# EEZ_DIB_AFE1_r1B3.net
KiCad netlist of a schematic drawn in EAGLE
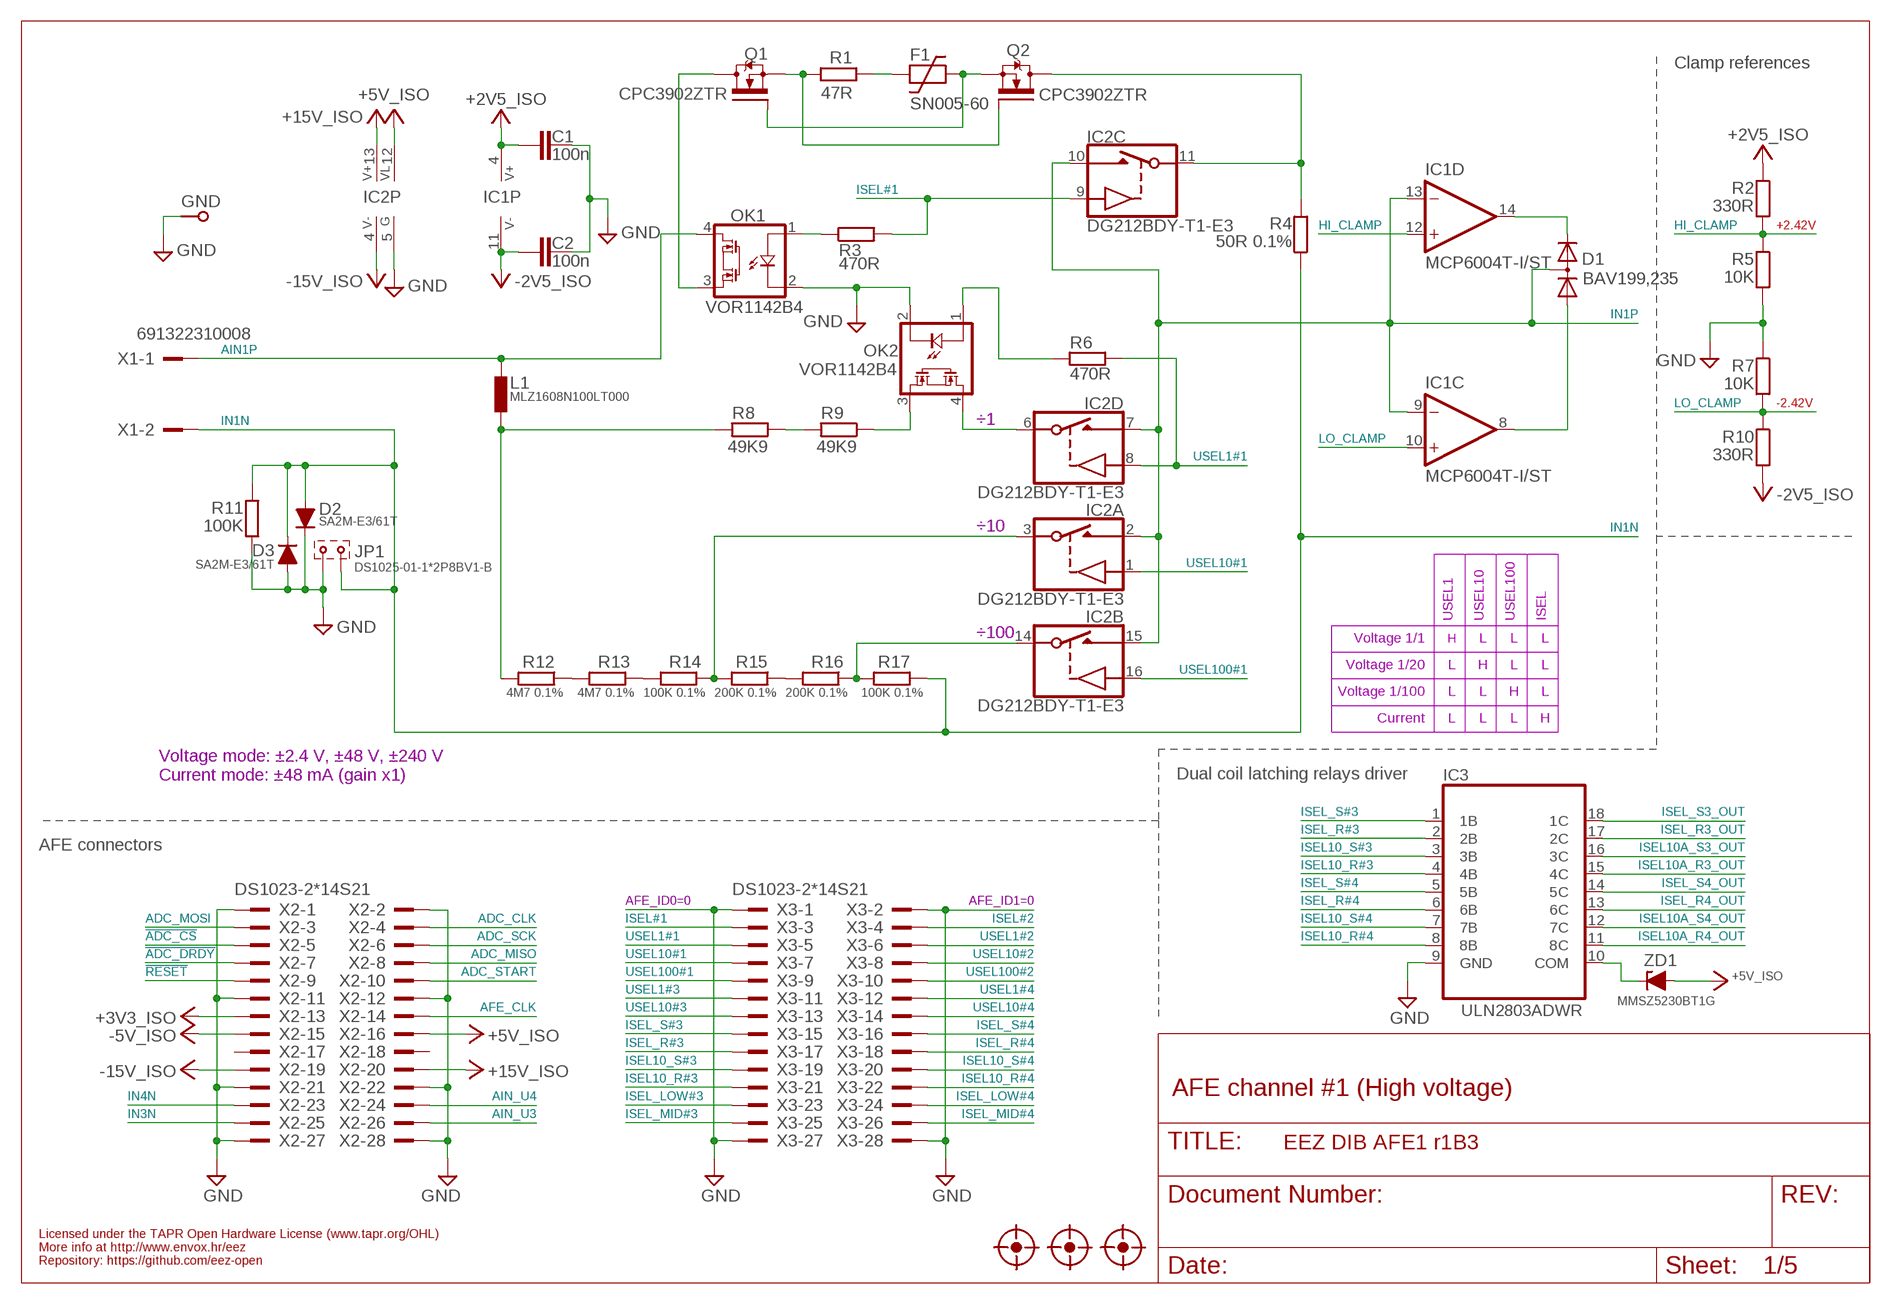
[diagram p0: schematic, sheet 1]
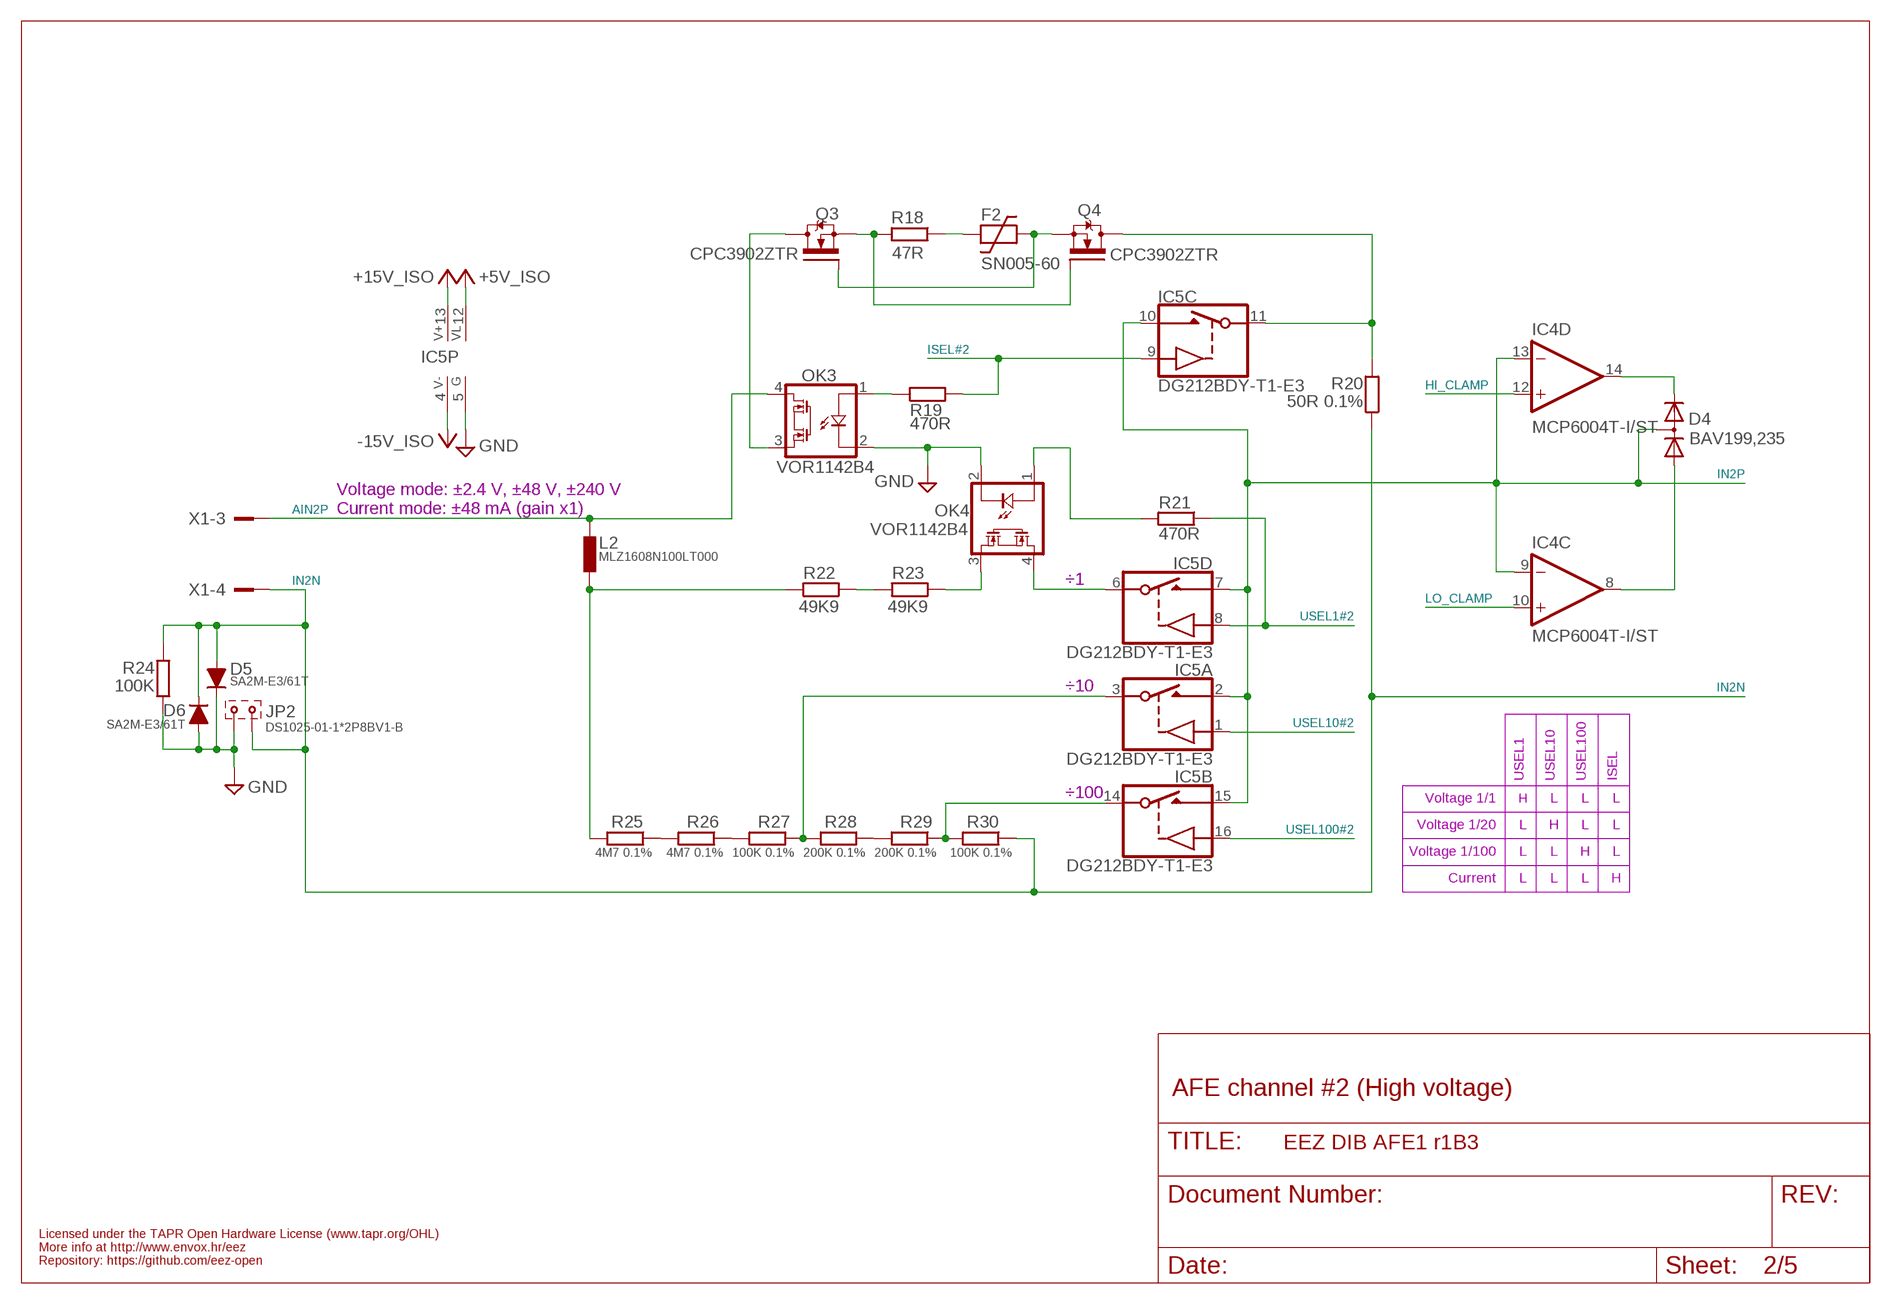
[diagram p1: schematic, sheet 2]
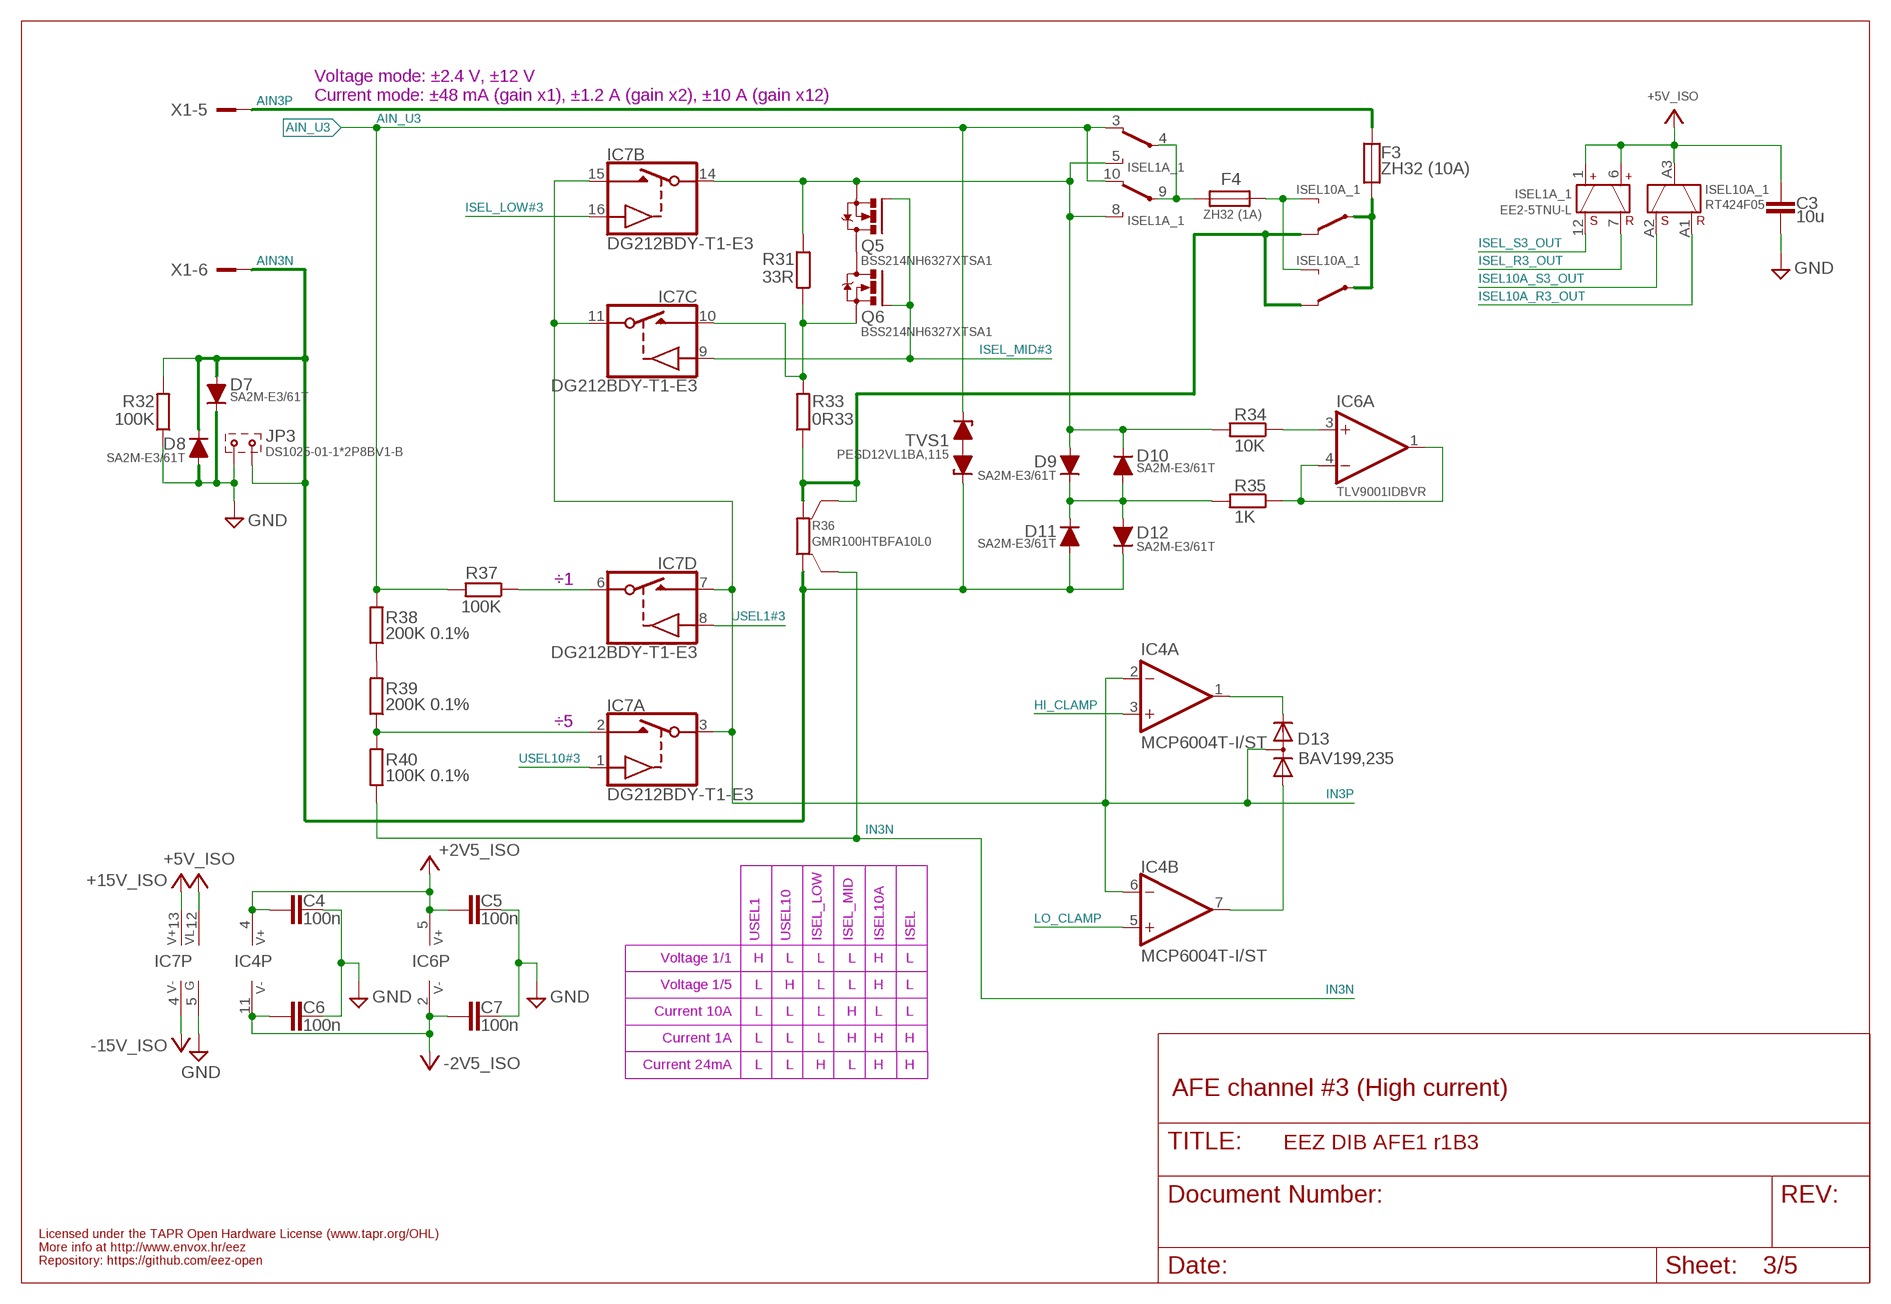
[diagram p2: schematic, sheet 3]
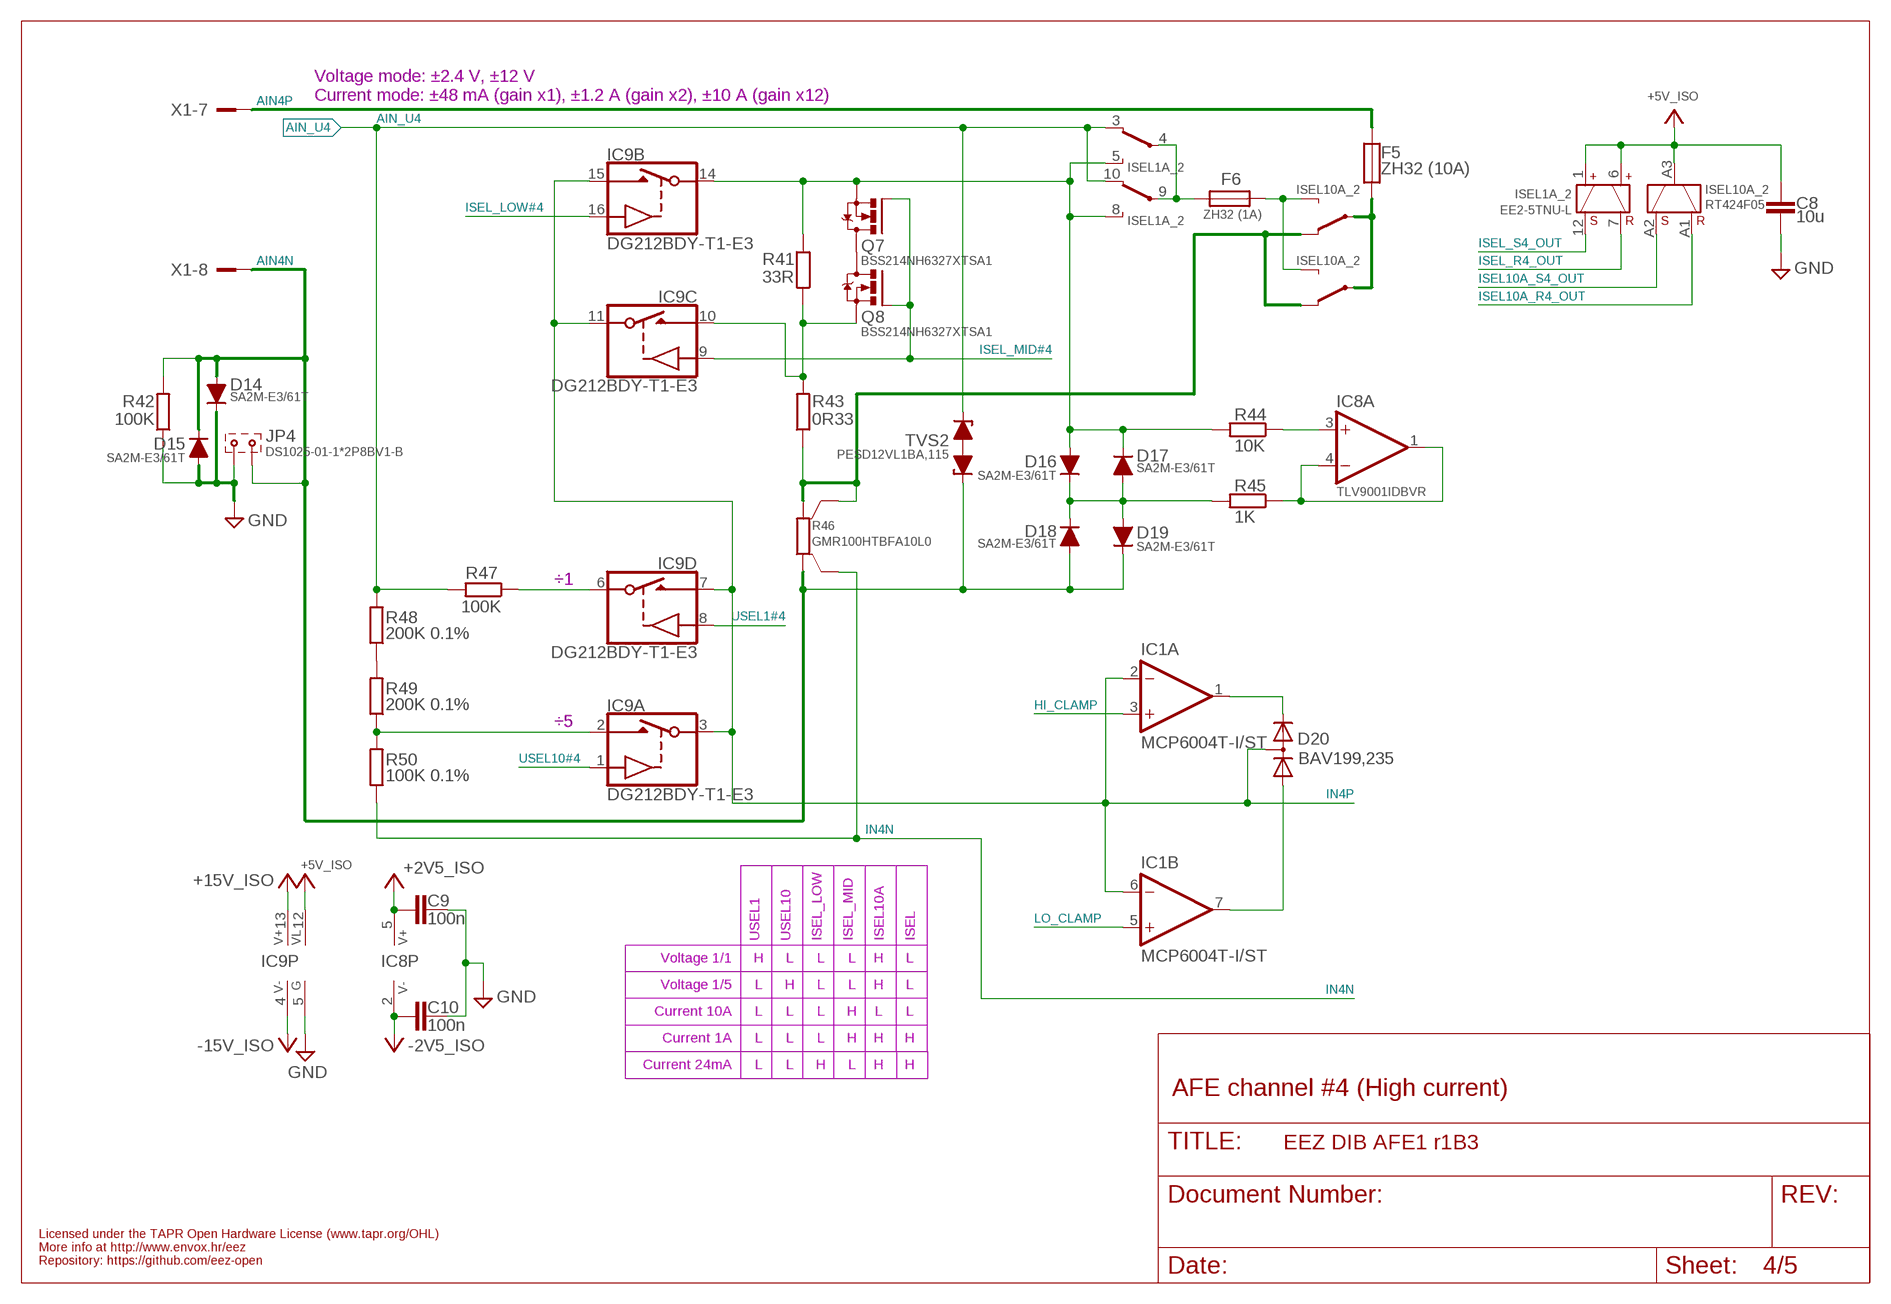
[diagram p3: schematic, sheet 4]
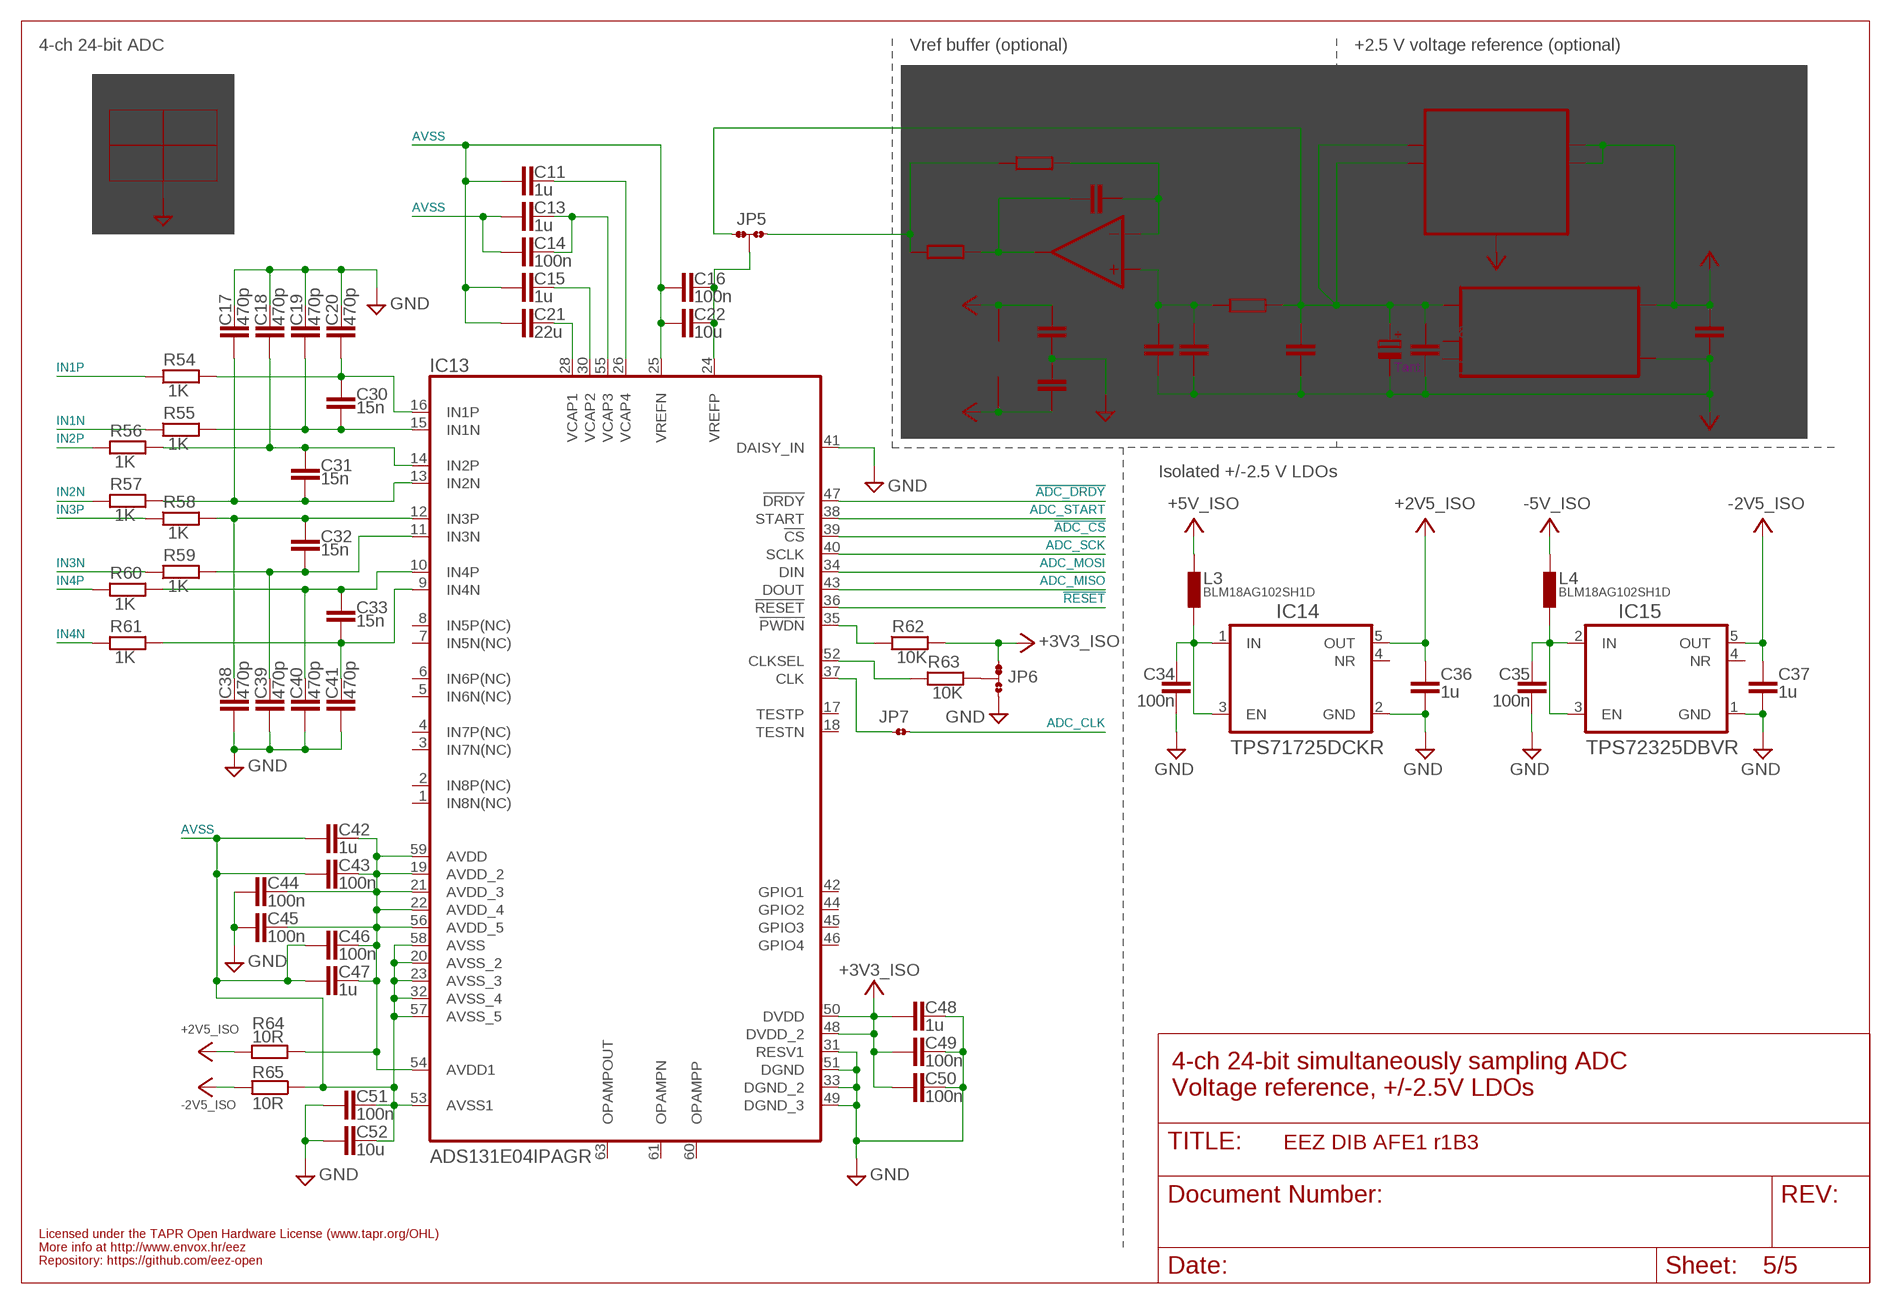
[diagram p4: schematic, sheet 5]

(export (version "E")
  (design (tool "Eeschema 10.0.6"))
  (components
    (comp (ref "C3")
      (value "10u")
      (footprint "eagle-import:C1206")
      (libsource (lib "eagle-import") (part "C-EUC1206"))
    )
    (comp (ref "C4")
      (value "100n")
      (footprint "eagle-import:C0603")
      (libsource (lib "eagle-import") (part "C-EUC0603"))
    )
    (comp (ref "C5")
      (value "100n")
      (footprint "eagle-import:C0603")
      (libsource (lib "eagle-import") (part "C-EUC0603"))
    )
    (comp (ref "C6")
      (value "100n")
      (footprint "eagle-import:C0603")
      (libsource (lib "eagle-import") (part "C-EUC0603"))
    )
    (comp (ref "C7")
      (value "100n")
      (footprint "eagle-import:C0603")
      (libsource (lib "eagle-import") (part "C-EUC0603"))
    )
    (comp (ref "D7")
      (value "SA2M-E3/61T")
      (footprint "eagle-import:SMA_NARROW")
      (libsource (lib "eagle-import") (part "DIODE_SMA-NARROW"))
    )
    (comp (ref "D8")
      (value "SA2M-E3/61T")
      (footprint "eagle-import:SMA_NARROW")
      (libsource (lib "eagle-import") (part "DIODE_SMA-NARROW"))
    )
    (comp (ref "D9")
      (value "SA2M-E3/61T")
      (footprint "eagle-import:SMA_NARROW")
      (libsource (lib "eagle-import") (part "DIODE_SMA-NARROW"))
    )
    (comp (ref "D10")
      (value "SA2M-E3/61T")
      (footprint "eagle-import:SMA_NARROW")
      (libsource (lib "eagle-import") (part "DIODE_SMA-NARROW"))
    )
    (comp (ref "D11")
      (value "SA2M-E3/61T")
      (footprint "eagle-import:SMA_NARROW")
      (libsource (lib "eagle-import") (part "DIODE_SMA-NARROW"))
    )
    (comp (ref "D12")
      (value "SA2M-E3/61T")
      (footprint "eagle-import:SMA_NARROW")
      (libsource (lib "eagle-import") (part "DIODE_SMA-NARROW"))
    )
    (comp (ref "D13")
      (value "BAV199,235")
      (footprint "eagle-import:SOT23")
      (libsource (lib "eagle-import") (part "BAV199"))
    )
    (comp (ref "F3")
      (value "ZH32 (10A)")
      (footprint "eagle-import:ZH32")
      (libsource (lib "eagle-import") (part "ZH32"))
    )
    (comp (ref "F4")
      (value "ZH32 (1A)")
      (footprint "eagle-import:ZH32")
      (libsource (lib "eagle-import") (part "ZH32"))
    )
    (comp (ref "IC4")
      (value "MCP6004T-I/ST")
      (footprint "eagle-import:PW(R-PDSO-G14)")
      (libsource (lib "eagle-import") (part "OPA4197PW"))
    )
    (comp (ref "IC6")
      (value "TLV9001IDBVR")
      (footprint "eagle-import:DBV5")
      (libsource (lib "eagle-import") (part "OPA376AIDBVR"))
    )
    (comp (ref "IC7")
      (value "DG212BDY-T1-E3")
      (footprint "eagle-import:SO16")
      (libsource (lib "eagle-import") (part "DG212BDY-T1-E3"))
    )
    (comp (ref "ISEL1A_1")
      (value "EE2-5TNU-L")
      (footprint "eagle-import:G6SK-2F")
      (libsource (lib "eagle-import") (part "G6SK-2F"))
    )
    (comp (ref "ISEL10A_1")
      (value "RT424F05")
      (footprint "eagle-import:RT424FXX")
      (libsource (lib "eagle-import") (part "RT424FXX"))
    )
    (comp (ref "JP3")
      (value "DS1025-01-1*2P8BV1-B")
      (footprint "eagle-import:2MM-2")
      (libsource (lib "eagle-import") (part "JUMPER-2PIN-2MM"))
    )
    (comp (ref "Q5")
      (value "BSS214NH6327XTSA1")
      (footprint "eagle-import:SOT103P240X110-3N")
      (fields
        (field (name "MPN") "2N7002-7-F")
        (field (name "MPN_1") "2N7002-7-F")
        (field (name "OC_FARNELL") "1713823")
        (field (name "OC_NEWARK") "25R5679")
        (field (name "PACKAGE") "SOT-23-3")
        (field (name "SUPPLIER") "DIODES INC.")
      )
      (libsource (lib "eagle-import") (part "2N7002"))
    )
    (comp (ref "Q6")
      (value "BSS214NH6327XTSA1")
      (footprint "eagle-import:SOT103P240X110-3N")
      (fields (field (name "MPN") "2N7002-7-F"))
      (libsource (lib "eagle-import") (part "2N7002"))
    )
    (comp (ref "R31")
      (value "33R")
      (footprint "eagle-import:R1206")
      (libsource (lib "eagle-import") (part "R-EU_R1206"))
    )
    (comp (ref "R32")
      (value "100K")
      (footprint "eagle-import:R1206")
      (libsource (lib "eagle-import") (part "R-EU_R1206"))
    )
    (comp (ref "R33")
      (value "0R33")
      (footprint "eagle-import:R1210")
      (libsource (lib "eagle-import") (part "R-EU_R1210"))
    )
    (comp (ref "R34")
      (value "10K")
      (footprint "eagle-import:R0805")
      (libsource (lib "eagle-import") (part "R-EU_R0805"))
    )
    (comp (ref "R35")
      (value "1K")
      (footprint "eagle-import:R0805")
      (libsource (lib "eagle-import") (part "R-EU_R0805"))
    )
    (comp (ref "R36")
      (value "GMR100HTBFA10L0")
      (footprint "eagle-import:R_2512-4WIRE")
      (libsource (lib "eagle-import") (part "R-EU_4WIRE2512"))
    )
    (comp (ref "R37")
      (value "100K")
      (footprint "eagle-import:R1206")
      (libsource (lib "eagle-import") (part "R-EU_R1206"))
    )
    (comp (ref "R38")
      (value "200K 0.1%")
      (footprint "eagle-import:R1206")
      (libsource (lib "eagle-import") (part "R-EU_R1206"))
    )
    (comp (ref "R39")
      (value "200K 0.1%")
      (footprint "eagle-import:R1206")
      (libsource (lib "eagle-import") (part "R-EU_R1206"))
    )
    (comp (ref "R40")
      (value "100K 0.1%")
      (footprint "eagle-import:R1206")
      (libsource (lib "eagle-import") (part "R-EU_R1206"))
    )
    (comp (ref "TVS1")
      (value "PESD12VL1BA,115")
      (footprint "eagle-import:SOD323-BIDIR")
      (libsource (lib "eagle-import") (part "PESDXL1BA"))
    )
    (comp (ref "X1")
      (value "691322310008")
      (footprint "eagle-import:691322310008")
      (libsource (lib "eagle-import") (part "691322310008"))
    )
    (comp (ref "D4")
      (value "BAV199,235")
      (footprint "eagle-import:SOT23")
      (libsource (lib "eagle-import") (part "BAV199"))
    )
    (comp (ref "D5")
      (value "SA2M-E3/61T")
      (footprint "eagle-import:SMA_NARROW")
      (libsource (lib "eagle-import") (part "DIODE_SMA-NARROW"))
    )
    (comp (ref "D6")
      (value "SA2M-E3/61T")
      (footprint "eagle-import:SMA_NARROW")
      (libsource (lib "eagle-import") (part "DIODE_SMA-NARROW"))
    )
    (comp (ref "F2")
      (value "SN005-60")
      (footprint "eagle-import:C1206-HV")
      (libsource (lib "eagle-import") (part "FUSE_RESETTABLE2"))
    )
    (comp (ref "IC5")
      (value "DG212BDY-T1-E3")
      (footprint "eagle-import:SO16")
      (libsource (lib "eagle-import") (part "DG212BDY-T1-E3"))
    )
    (comp (ref "JP2")
      (value "DS1025-01-1*2P8BV1-B")
      (footprint "eagle-import:2MM-2")
      (libsource (lib "eagle-import") (part "JUMPER-2PIN-2MM"))
    )
    (comp (ref "L2")
      (value "MLZ1608N100LT000")
      (footprint "eagle-import:BEAD0603")
      (libsource (lib "eagle-import") (part "FERRITE_BEAD0603"))
    )
    (comp (ref "OK3")
      (value "VOR1142B4")
      (footprint "eagle-import:DIL4-SMD")
      (libsource (lib "eagle-import") (part "VOR1142B4"))
    )
    (comp (ref "OK4")
      (value "VOR1142B4")
      (footprint "eagle-import:DIL4-SMD")
      (libsource (lib "eagle-import") (part "VOR1142B4"))
    )
    (comp (ref "Q3")
      (value "CPC3902ZTR")
      (footprint "eagle-import:SOT230P700X180-4N")
      (libsource (lib "eagle-import") (part "BSP129SOT-223"))
    )
    (comp (ref "Q4")
      (value "CPC3902ZTR")
      (footprint "eagle-import:SOT230P700X180-4N")
      (libsource (lib "eagle-import") (part "BSP129SOT-223"))
    )
    (comp (ref "R18")
      (value "47R")
      (footprint "eagle-import:R0805")
      (libsource (lib "eagle-import") (part "R-EU_R0805"))
    )
    (comp (ref "R19")
      (value "470R")
      (footprint "eagle-import:R0805")
      (libsource (lib "eagle-import") (part "R-EU_R0805"))
    )
    (comp (ref "R20")
      (value "50R 0.1%")
      (footprint "eagle-import:R1206")
      (libsource (lib "eagle-import") (part "R-EU_R1206"))
    )
    (comp (ref "R21")
      (value "470R")
      (footprint "eagle-import:R0805")
      (libsource (lib "eagle-import") (part "R-EU_R0805"))
    )
    (comp (ref "R22")
      (value "49K9")
      (footprint "eagle-import:R1206")
      (libsource (lib "eagle-import") (part "R-EU_R1206"))
    )
    (comp (ref "R23")
      (value "49K9")
      (footprint "eagle-import:R1206")
      (libsource (lib "eagle-import") (part "R-EU_R1206"))
    )
    (comp (ref "R24")
      (value "100K")
      (footprint "eagle-import:R1206")
      (libsource (lib "eagle-import") (part "R-EU_R1206"))
    )
    (comp (ref "R25")
      (value "4M7 0.1%")
      (footprint "eagle-import:R1206")
      (libsource (lib "eagle-import") (part "R-EU_R1206"))
    )
    (comp (ref "R26")
      (value "4M7 0.1%")
      (footprint "eagle-import:R1206")
      (libsource (lib "eagle-import") (part "R-EU_R1206"))
    )
    (comp (ref "R27")
      (value "100K 0.1%")
      (footprint "eagle-import:R1206")
      (libsource (lib "eagle-import") (part "R-EU_R1206"))
    )
    (comp (ref "R28")
      (value "200K 0.1%")
      (footprint "eagle-import:R1206")
      (libsource (lib "eagle-import") (part "R-EU_R1206"))
    )
    (comp (ref "R29")
      (value "200K 0.1%")
      (footprint "eagle-import:R1206")
      (libsource (lib "eagle-import") (part "R-EU_R1206"))
    )
    (comp (ref "R30")
      (value "100K 0.1%")
      (footprint "eagle-import:R1206")
      (libsource (lib "eagle-import") (part "R-EU_R1206"))
    )
    (comp (ref "C11")
      (value "1u")
      (footprint "eagle-import:C0805")
      (libsource (lib "eagle-import") (part "C-EUC0805"))
    )
    (comp (ref "C12")
      (value "N.C.")
      (footprint "eagle-import:C0805")
      (libsource (lib "eagle-import") (part "C-EUC0805"))
    )
    (comp (ref "C13")
      (value "1u")
      (footprint "eagle-import:C0805")
      (libsource (lib "eagle-import") (part "C-EUC0805"))
    )
    (comp (ref "C14")
      (value "100n")
      (footprint "eagle-import:C0603")
      (libsource (lib "eagle-import") (part "C-EUC0603"))
    )
    (comp (ref "C15")
      (value "1u")
      (footprint "eagle-import:C0805")
      (libsource (lib "eagle-import") (part "C-EUC0805"))
    )
    (comp (ref "C16")
      (value "100n")
      (footprint "eagle-import:C0603")
      (libsource (lib "eagle-import") (part "C-EUC0603"))
    )
    (comp (ref "C17")
      (value "470p")
      (footprint "eagle-import:C0603")
      (libsource (lib "eagle-import") (part "C-EUC0603"))
    )
    (comp (ref "C18")
      (value "470p")
      (footprint "eagle-import:C0603")
      (libsource (lib "eagle-import") (part "C-EUC0603"))
    )
    (comp (ref "C19")
      (value "470p")
      (footprint "eagle-import:C0603")
      (libsource (lib "eagle-import") (part "C-EUC0603"))
    )
    (comp (ref "C20")
      (value "470p")
      (footprint "eagle-import:C0603")
      (libsource (lib "eagle-import") (part "C-EUC0603"))
    )
    (comp (ref "C21")
      (value "22u")
      (footprint "eagle-import:C1206")
      (libsource (lib "eagle-import") (part "C-EUC1206"))
    )
    (comp (ref "C22")
      (value "10u")
      (footprint "eagle-import:C1206")
      (libsource (lib "eagle-import") (part "C-EUC1206"))
    )
    (comp (ref "C23")
      (value "N.C.")
      (footprint "eagle-import:C0603")
      (libsource (lib "eagle-import") (part "C-EUC0603"))
    )
    (comp (ref "C24")
      (value "N.C.")
      (footprint "eagle-import:C1206")
      (libsource (lib "eagle-import") (part "C-EUC1206"))
    )
    (comp (ref "C25")
      (value "N.C.")
      (footprint "eagle-import:C1206")
      (libsource (lib "eagle-import") (part "C-EUC1206"))
    )
    (comp (ref "C26")
      (value "N.C.")
      (footprint "eagle-import:C1206")
      (libsource (lib "eagle-import") (part "C-EUC1206"))
    )
    (comp (ref "C27")
      (value "N.C.")
      (footprint "eagle-import:C1206")
      (libsource (lib "eagle-import") (part "C-EUC1206"))
    )
    (comp (ref "C28")
      (value "N.C.")
      (footprint "eagle-import:EC1206")
      (libsource (lib "eagle-import") (part "ECAP1206"))
    )
    (comp (ref "C28A")
      (value "N.C.")
      (footprint "eagle-import:C050-075X110")
      (libsource (lib "eagle-import") (part "C-EU7.5X11"))
    )
    (comp (ref "C29")
      (value "N.C.")
      (footprint "eagle-import:C0603")
      (libsource (lib "eagle-import") (part "C-EUC0603"))
    )
    (comp (ref "C30")
      (value "15n")
      (footprint "eagle-import:C0603")
      (libsource (lib "eagle-import") (part "C-EUC0603"))
    )
    (comp (ref "C31")
      (value "15n")
      (footprint "eagle-import:C0603")
      (libsource (lib "eagle-import") (part "C-EUC0603"))
    )
    (comp (ref "C32")
      (value "15n")
      (footprint "eagle-import:C0603")
      (libsource (lib "eagle-import") (part "C-EUC0603"))
    )
    (comp (ref "C33")
      (value "15n")
      (footprint "eagle-import:C0603")
      (libsource (lib "eagle-import") (part "C-EUC0603"))
    )
    (comp (ref "C34")
      (value "100n")
      (footprint "eagle-import:C0603")
      (libsource (lib "eagle-import") (part "C-EUC0603"))
    )
    (comp (ref "C35")
      (value "100n")
      (footprint "eagle-import:C0603")
      (libsource (lib "eagle-import") (part "C-EUC0603"))
    )
    (comp (ref "C36")
      (value "1u")
      (footprint "eagle-import:C0805")
      (libsource (lib "eagle-import") (part "C-EUC0805"))
    )
    (comp (ref "C37")
      (value "1u")
      (footprint "eagle-import:C0805")
      (libsource (lib "eagle-import") (part "C-EUC0805"))
    )
    (comp (ref "C38")
      (value "470p")
      (footprint "eagle-import:C0603")
      (libsource (lib "eagle-import") (part "C-EUC0603"))
    )
    (comp (ref "C39")
      (value "470p")
      (footprint "eagle-import:C0603")
      (libsource (lib "eagle-import") (part "C-EUC0603"))
    )
    (comp (ref "C40")
      (value "470p")
      (footprint "eagle-import:C0603")
      (libsource (lib "eagle-import") (part "C-EUC0603"))
    )
    (comp (ref "C41")
      (value "470p")
      (footprint "eagle-import:C0603")
      (libsource (lib "eagle-import") (part "C-EUC0603"))
    )
    (comp (ref "C42")
      (value "1u")
      (footprint "eagle-import:C0805")
      (libsource (lib "eagle-import") (part "C-EUC0805"))
    )
    (comp (ref "C43")
      (value "100n")
      (footprint "eagle-import:C0603")
      (libsource (lib "eagle-import") (part "C-EUC0603"))
    )
    (comp (ref "C44")
      (value "100n")
      (footprint "eagle-import:C0603")
      (libsource (lib "eagle-import") (part "C-EUC0603"))
    )
    (comp (ref "C45")
      (value "100n")
      (footprint "eagle-import:C0603")
      (libsource (lib "eagle-import") (part "C-EUC0603"))
    )
    (comp (ref "C46")
      (value "100n")
      (footprint "eagle-import:C0603")
      (libsource (lib "eagle-import") (part "C-EUC0603"))
    )
    (comp (ref "C47")
      (value "1u")
      (footprint "eagle-import:C0805")
      (libsource (lib "eagle-import") (part "C-EUC0805"))
    )
    (comp (ref "C48")
      (value "1u")
      (footprint "eagle-import:C0805")
      (libsource (lib "eagle-import") (part "C-EUC0805"))
    )
    (comp (ref "C49")
      (value "100n")
      (footprint "eagle-import:C0603")
      (libsource (lib "eagle-import") (part "C-EUC0603"))
    )
    (comp (ref "C50")
      (value "100n")
      (footprint "eagle-import:C0603")
      (libsource (lib "eagle-import") (part "C-EUC0603"))
    )
    (comp (ref "C51")
      (value "100n")
      (footprint "eagle-import:C0603")
      (libsource (lib "eagle-import") (part "C-EUC0603"))
    )
    (comp (ref "C52")
      (value "10u")
      (footprint "eagle-import:C1206")
      (libsource (lib "eagle-import") (part "C-EUC1206"))
    )
    (comp (ref "IC10")
      (value "N.C.")
      (footprint "eagle-import:MSOP-8_MS_LIT")
      (libsource (lib "eagle-import") (part "LTC6655BHMS8"))
    )
    (comp (ref "IC11")
      (value "N.C.")
      (footprint "eagle-import:DBV5")
      (libsource (lib "eagle-import") (part "OPA376AIDBVR"))
    )
    (comp (ref "IC12")
      (value "N.C.")
      (footprint "eagle-import:SOIC127P600X175-8N")
      (libsource (lib "eagle-import") (part "REF50XX"))
    )
    (comp (ref "IC13")
      (value "ADS131E04IPAGR")
      (footprint "eagle-import:PAG64")
      (libsource (lib "eagle-import") (part "ADS131E0XIPAG"))
    )
    (comp (ref "IC14")
      (value "TPS71725DCKR")
      (footprint "eagle-import:DCK5")
      (libsource (lib "eagle-import") (part "TPS71725DCKR"))
    )
    (comp (ref "IC15")
      (value "TPS72325DBVR")
      (footprint "eagle-import:DBV5")
      (libsource (lib "eagle-import") (part "TPS72325DBVR"))
    )
    (comp (ref "JP5")
      (value "JP3-CUT-0805-ROTATED")
      (footprint "eagle-import:JP3-0805-CUT2")
      (libsource (lib "eagle-import") (part "JP3-CUT-0805-ROTATED"))
    )
    (comp (ref "JP6")
      (value "JP3-CUT-0805-ROTATED")
      (footprint "eagle-import:JP3-0805-CUT2")
      (libsource (lib "eagle-import") (part "JP3-CUT-0805-ROTATED"))
    )
    (comp (ref "JP7")
      (value "JP2-CUT-0805")
      (footprint "eagle-import:R_0805")
      (libsource (lib "eagle-import") (part "JP2-CUT-0805"))
    )
    (comp (ref "L3")
      (value "BLM18AG102SH1D")
      (footprint "eagle-import:BEAD0603")
      (libsource (lib "eagle-import") (part "FERRITE_BEAD0603"))
    )
    (comp (ref "L4")
      (value "BLM18AG102SH1D")
      (footprint "eagle-import:BEAD0603")
      (libsource (lib "eagle-import") (part "FERRITE_BEAD0603"))
    )
    (comp (ref "R51")
      (value "N.C.")
      (footprint "eagle-import:R0805")
      (libsource (lib "eagle-import") (part "R-EU_R0805"))
    )
    (comp (ref "R52")
      (value "N.C.")
      (footprint "eagle-import:R0805")
      (libsource (lib "eagle-import") (part "R-EU_R0805"))
    )
    (comp (ref "R53")
      (value "N.C.")
      (footprint "eagle-import:R0805")
      (libsource (lib "eagle-import") (part "R-EU_R0805"))
    )
    (comp (ref "R54")
      (value "1K")
      (footprint "eagle-import:R0805")
      (libsource (lib "eagle-import") (part "R-EU_R0805"))
    )
    (comp (ref "R55")
      (value "1K")
      (footprint "eagle-import:R0805")
      (libsource (lib "eagle-import") (part "R-EU_R0805"))
    )
    (comp (ref "R56")
      (value "1K")
      (footprint "eagle-import:R0805")
      (libsource (lib "eagle-import") (part "R-EU_R0805"))
    )
    (comp (ref "R57")
      (value "1K")
      (footprint "eagle-import:R0805")
      (libsource (lib "eagle-import") (part "R-EU_R0805"))
    )
    (comp (ref "R58")
      (value "1K")
      (footprint "eagle-import:R0805")
      (libsource (lib "eagle-import") (part "R-EU_R0805"))
    )
    (comp (ref "R59")
      (value "1K")
      (footprint "eagle-import:R0805")
      (libsource (lib "eagle-import") (part "R-EU_R0805"))
    )
    (comp (ref "R60")
      (value "1K")
      (footprint "eagle-import:R0805")
      (libsource (lib "eagle-import") (part "R-EU_R0805"))
    )
    (comp (ref "R61")
      (value "1K")
      (footprint "eagle-import:R0805")
      (libsource (lib "eagle-import") (part "R-EU_R0805"))
    )
    (comp (ref "R62")
      (value "10K")
      (footprint "eagle-import:R0805")
      (libsource (lib "eagle-import") (part "R-EU_R0805"))
    )
    (comp (ref "R63")
      (value "10K")
      (footprint "eagle-import:R0805")
      (libsource (lib "eagle-import") (part "R-EU_R0805"))
    )
    (comp (ref "R64")
      (value "10R")
      (footprint "eagle-import:R1206")
      (libsource (lib "eagle-import") (part "R-EU_R1206"))
    )
    (comp (ref "R65")
      (value "10R")
      (footprint "eagle-import:R1206")
      (libsource (lib "eagle-import") (part "R-EU_R1206"))
    )
    (comp (ref "S1")
      (value "N.C.")
      (footprint "eagle-import:2118732-2")
      (libsource (lib "eagle-import") (part "2118732-2"))
    )
    (comp (ref "C1")
      (value "100n")
      (footprint "eagle-import:C0603")
      (libsource (lib "eagle-import") (part "C-EUC0603"))
    )
    (comp (ref "C2")
      (value "100n")
      (footprint "eagle-import:C0603")
      (libsource (lib "eagle-import") (part "C-EUC0603"))
    )
    (comp (ref "D1")
      (value "BAV199,235")
      (footprint "eagle-import:SOT23")
      (libsource (lib "eagle-import") (part "BAV199"))
    )
    (comp (ref "D2")
      (value "SA2M-E3/61T")
      (footprint "eagle-import:SMA_NARROW")
      (libsource (lib "eagle-import") (part "DIODE_SMA-NARROW"))
    )
    (comp (ref "D3")
      (value "SA2M-E3/61T")
      (footprint "eagle-import:SMA_NARROW")
      (libsource (lib "eagle-import") (part "DIODE_SMA-NARROW"))
    )
    (comp (ref "F1")
      (value "SN005-60")
      (footprint "eagle-import:C1206-HV")
      (libsource (lib "eagle-import") (part "FUSE_RESETTABLE2"))
    )
    (comp (ref "FM1")
      (value "FIDUCIAL_2")
      (footprint "eagle-import:FIDUCIAL_DUAL")
      (libsource (lib "eagle-import") (part "FIDUCIAL_2"))
    )
    (comp (ref "FM2")
      (value "FIDUCIAL_2")
      (footprint "eagle-import:FIDUCIAL_DUAL")
      (libsource (lib "eagle-import") (part "FIDUCIAL_2"))
    )
    (comp (ref "FM3")
      (value "FIDUCIAL_2")
      (footprint "eagle-import:FIDUCIAL_DUAL")
      (libsource (lib "eagle-import") (part "FIDUCIAL_2"))
    )
    (comp (ref "GND")
      (value "PCB_TEST_TABSHIELD")
      (footprint "eagle-import:PCB_SHIELD_TAB")
      (libsource (lib "eagle-import") (part "PCB_TEST_TABSHIELD"))
    )
    (comp (ref "IC1")
      (value "MCP6004T-I/ST")
      (footprint "eagle-import:PW(R-PDSO-G14)")
      (libsource (lib "eagle-import") (part "OPA4197PW"))
    )
    (comp (ref "IC2")
      (value "DG212BDY-T1-E3")
      (footprint "eagle-import:SO16")
      (libsource (lib "eagle-import") (part "DG212BDY-T1-E3"))
    )
    (comp (ref "IC3")
      (value "ULN2803ADWR")
      (footprint "eagle-import:DW18_TEX-M")
      (libsource (lib "eagle-import") (part "ULN2803ADWR"))
    )
    (comp (ref "JP1")
      (value "DS1025-01-1*2P8BV1-B")
      (footprint "eagle-import:2MM-2")
      (libsource (lib "eagle-import") (part "JUMPER-2PIN-2MM"))
    )
    (comp (ref "L1")
      (value "MLZ1608N100LT000")
      (footprint "eagle-import:BEAD0603")
      (libsource (lib "eagle-import") (part "FERRITE_BEAD0603"))
    )
    (comp (ref "OK1")
      (value "VOR1142B4")
      (footprint "eagle-import:DIL4-SMD")
      (libsource (lib "eagle-import") (part "VOR1142B4"))
    )
    (comp (ref "OK2")
      (value "VOR1142B4")
      (footprint "eagle-import:DIL4-SMD")
      (libsource (lib "eagle-import") (part "VOR1142B4"))
    )
    (comp (ref "Q1")
      (value "CPC3902ZTR")
      (footprint "eagle-import:SOT230P700X180-4N")
      (libsource (lib "eagle-import") (part "BSP129SOT-223"))
    )
    (comp (ref "Q2")
      (value "CPC3902ZTR")
      (footprint "eagle-import:SOT230P700X180-4N")
      (libsource (lib "eagle-import") (part "BSP129SOT-223"))
    )
    (comp (ref "R1")
      (value "47R")
      (footprint "eagle-import:R0805")
      (libsource (lib "eagle-import") (part "R-EU_R0805"))
    )
    (comp (ref "R2")
      (value "330R")
      (footprint "eagle-import:R0805")
      (libsource (lib "eagle-import") (part "R-EU_R0805"))
    )
    (comp (ref "R3")
      (value "470R")
      (footprint "eagle-import:R0805")
      (libsource (lib "eagle-import") (part "R-EU_R0805"))
    )
    (comp (ref "R4")
      (value "50R 0.1%")
      (footprint "eagle-import:R1206")
      (libsource (lib "eagle-import") (part "R-EU_R1206"))
    )
    (comp (ref "R5")
      (value "10K")
      (footprint "eagle-import:R0805")
      (libsource (lib "eagle-import") (part "R-EU_R0805"))
    )
    (comp (ref "R6")
      (value "470R")
      (footprint "eagle-import:R0805")
      (libsource (lib "eagle-import") (part "R-EU_R0805"))
    )
    (comp (ref "R7")
      (value "10K")
      (footprint "eagle-import:R0805")
      (libsource (lib "eagle-import") (part "R-EU_R0805"))
    )
    (comp (ref "R8")
      (value "49K9")
      (footprint "eagle-import:R1206")
      (libsource (lib "eagle-import") (part "R-EU_R1206"))
    )
    (comp (ref "R9")
      (value "49K9")
      (footprint "eagle-import:R1206")
      (libsource (lib "eagle-import") (part "R-EU_R1206"))
    )
    (comp (ref "R10")
      (value "330R")
      (footprint "eagle-import:R0805")
      (libsource (lib "eagle-import") (part "R-EU_R0805"))
    )
    (comp (ref "R11")
      (value "100K")
      (footprint "eagle-import:R1206")
      (libsource (lib "eagle-import") (part "R-EU_R1206"))
    )
    (comp (ref "R12")
      (value "4M7 0.1%")
      (footprint "eagle-import:R1206")
      (libsource (lib "eagle-import") (part "R-EU_R1206"))
    )
    (comp (ref "R13")
      (value "4M7 0.1%")
      (footprint "eagle-import:R1206")
      (libsource (lib "eagle-import") (part "R-EU_R1206"))
    )
    (comp (ref "R14")
      (value "100K 0.1%")
      (footprint "eagle-import:R1206")
      (libsource (lib "eagle-import") (part "R-EU_R1206"))
    )
    (comp (ref "R15")
      (value "200K 0.1%")
      (footprint "eagle-import:R1206")
      (libsource (lib "eagle-import") (part "R-EU_R1206"))
    )
    (comp (ref "R16")
      (value "200K 0.1%")
      (footprint "eagle-import:R1206")
      (libsource (lib "eagle-import") (part "R-EU_R1206"))
    )
    (comp (ref "R17")
      (value "100K 0.1%")
      (footprint "eagle-import:R1206")
      (libsource (lib "eagle-import") (part "R-EU_R1206"))
    )
    (comp (ref "X2")
      (value "DS1023-2*14S21")
      (footprint "eagle-import:TSW-114-07-F-D")
      (libsource (lib "eagle-import") (part "TSW-114-07-F-D"))
    )
    (comp (ref "X3")
      (value "DS1023-2*14S21")
      (footprint "eagle-import:TSW-114-07-F-D")
      (libsource (lib "eagle-import") (part "TSW-114-07-F-D"))
    )
    (comp (ref "ZD1")
      (value "MMSZ5230BT1G")
      (footprint "eagle-import:SOD123")
      (libsource (lib "eagle-import") (part "ZENER-DIODESOD123"))
    )
    (comp (ref "C8")
      (value "10u")
      (footprint "eagle-import:C1206")
      (libsource (lib "eagle-import") (part "C-EUC1206"))
    )
    (comp (ref "C9")
      (value "100n")
      (footprint "eagle-import:C0603")
      (libsource (lib "eagle-import") (part "C-EUC0603"))
    )
    (comp (ref "C10")
      (value "100n")
      (footprint "eagle-import:C0603")
      (libsource (lib "eagle-import") (part "C-EUC0603"))
    )
    (comp (ref "D14")
      (value "SA2M-E3/61T")
      (footprint "eagle-import:SMA_NARROW")
      (libsource (lib "eagle-import") (part "DIODE_SMA-NARROW"))
    )
    (comp (ref "D15")
      (value "SA2M-E3/61T")
      (footprint "eagle-import:SMA_NARROW")
      (libsource (lib "eagle-import") (part "DIODE_SMA-NARROW"))
    )
    (comp (ref "D16")
      (value "SA2M-E3/61T")
      (footprint "eagle-import:SMA_NARROW")
      (libsource (lib "eagle-import") (part "DIODE_SMA-NARROW"))
    )
    (comp (ref "D17")
      (value "SA2M-E3/61T")
      (footprint "eagle-import:SMA_NARROW")
      (libsource (lib "eagle-import") (part "DIODE_SMA-NARROW"))
    )
    (comp (ref "D18")
      (value "SA2M-E3/61T")
      (footprint "eagle-import:SMA_NARROW")
      (libsource (lib "eagle-import") (part "DIODE_SMA-NARROW"))
    )
    (comp (ref "D19")
      (value "SA2M-E3/61T")
      (footprint "eagle-import:SMA_NARROW")
      (libsource (lib "eagle-import") (part "DIODE_SMA-NARROW"))
    )
    (comp (ref "D20")
      (value "BAV199,235")
      (footprint "eagle-import:SOT23")
      (libsource (lib "eagle-import") (part "BAV199"))
    )
    (comp (ref "F5")
      (value "ZH32 (10A)")
      (footprint "eagle-import:ZH32")
      (libsource (lib "eagle-import") (part "ZH32"))
    )
    (comp (ref "F6")
      (value "ZH32 (1A)")
      (footprint "eagle-import:ZH32")
      (libsource (lib "eagle-import") (part "ZH32"))
    )
    (comp (ref "IC8")
      (value "TLV9001IDBVR")
      (footprint "eagle-import:DBV5")
      (libsource (lib "eagle-import") (part "OPA376AIDBVR"))
    )
    (comp (ref "IC9")
      (value "DG212BDY-T1-E3")
      (footprint "eagle-import:SO16")
      (libsource (lib "eagle-import") (part "DG212BDY-T1-E3"))
    )
    (comp (ref "ISEL1A_2")
      (value "EE2-5TNU-L")
      (footprint "eagle-import:G6SK-2F")
      (libsource (lib "eagle-import") (part "G6SK-2F"))
    )
    (comp (ref "ISEL10A_2")
      (value "RT424F05")
      (footprint "eagle-import:RT424FXX")
      (libsource (lib "eagle-import") (part "RT424FXX"))
    )
    (comp (ref "JP4")
      (value "DS1025-01-1*2P8BV1-B")
      (footprint "eagle-import:2MM-2")
      (libsource (lib "eagle-import") (part "JUMPER-2PIN-2MM"))
    )
    (comp (ref "Q7")
      (value "BSS214NH6327XTSA1")
      (footprint "eagle-import:SOT103P240X110-3N")
      (fields
        (field (name "MPN") "2N7002-7-F")
        (field (name "MPN_1") "2N7002-7-F")
        (field (name "OC_FARNELL") "1713823")
        (field (name "OC_NEWARK") "25R5679")
        (field (name "PACKAGE") "SOT-23-3")
        (field (name "SUPPLIER") "DIODES INC.")
      )
      (libsource (lib "eagle-import") (part "2N7002"))
    )
    (comp (ref "Q8")
      (value "BSS214NH6327XTSA1")
      (footprint "eagle-import:SOT103P240X110-3N")
      (fields (field (name "MPN") "2N7002-7-F"))
      (libsource (lib "eagle-import") (part "2N7002"))
    )
    (comp (ref "R41")
      (value "33R")
      (footprint "eagle-import:R1206")
      (libsource (lib "eagle-import") (part "R-EU_R1206"))
    )
    (comp (ref "R42")
      (value "100K")
      (footprint "eagle-import:R1206")
      (libsource (lib "eagle-import") (part "R-EU_R1206"))
    )
    (comp (ref "R43")
      (value "0R33")
      (footprint "eagle-import:R1210")
      (libsource (lib "eagle-import") (part "R-EU_R1210"))
    )
    (comp (ref "R44")
      (value "10K")
      (footprint "eagle-import:R0805")
      (libsource (lib "eagle-import") (part "R-EU_R0805"))
    )
    (comp (ref "R45")
      (value "1K")
      (footprint "eagle-import:R0805")
      (libsource (lib "eagle-import") (part "R-EU_R0805"))
    )
    (comp (ref "R46")
      (value "GMR100HTBFA10L0")
      (footprint "eagle-import:R_2512-4WIRE")
      (libsource (lib "eagle-import") (part "R-EU_4WIRE2512"))
    )
    (comp (ref "R47")
      (value "100K")
      (footprint "eagle-import:R1206")
      (libsource (lib "eagle-import") (part "R-EU_R1206"))
    )
    (comp (ref "R48")
      (value "200K 0.1%")
      (footprint "eagle-import:R1206")
      (libsource (lib "eagle-import") (part "R-EU_R1206"))
    )
    (comp (ref "R49")
      (value "200K 0.1%")
      (footprint "eagle-import:R1206")
      (libsource (lib "eagle-import") (part "R-EU_R1206"))
    )
    (comp (ref "R50")
      (value "100K 0.1%")
      (footprint "eagle-import:R1206")
      (libsource (lib "eagle-import") (part "R-EU_R1206"))
    )
    (comp (ref "TVS2")
      (value "PESD12VL1BA,115")
      (footprint "eagle-import:SOD323-BIDIR")
      (libsource (lib "eagle-import") (part "PESDXL1BA"))
    )
  )
  (nets
    (net (code "1") (name "+2V5_ISO") (class "Default")
      (node (ref "C1") (pin "2") (pinfunction "2_2") (pintype "passive"))
      (node (ref "C36") (pin "2") (pinfunction "2_2") (pintype "passive"))
      (node (ref "C4") (pin "2") (pinfunction "2_2") (pintype "passive"))
      (node (ref "C5") (pin "2") (pinfunction "2_2") (pintype "passive"))
      (node (ref "C9") (pin "2") (pinfunction "2_2") (pintype "passive"))
      (node (ref "IC1") (pin "4") (pinfunction "V+_4") (pintype "power_in"))
      (node (ref "IC14") (pin "5") (pinfunction "OUT_5") (pintype "passive"))
      (node (ref "IC4") (pin "4") (pinfunction "V+_4") (pintype "power_in"))
      (node (ref "IC6") (pin "5") (pinfunction "V+_5") (pintype "power_in"))
      (node (ref "IC8") (pin "5") (pinfunction "V+_5") (pintype "power_in"))
      (node (ref "R2") (pin "1") (pinfunction "1_1") (pintype "passive"))
      (node (ref "R64") (pin "1") (pinfunction "1_1") (pintype "passive"))
    )
    (net (code "2") (name "+3V3_ISO") (class "Default")
      (node (ref "C48") (pin "1") (pinfunction "1_1") (pintype "passive"))
      (node (ref "C49") (pin "2") (pinfunction "2_2") (pintype "passive"))
      (node (ref "C50") (pin "2") (pinfunction "2_2") (pintype "passive"))
      (node (ref "IC13") (pin "48") (pinfunction "DVDD_2_48") (pintype "power_in"))
      (node (ref "IC13") (pin "50") (pinfunction "DVDD_50") (pintype "power_in"))
      (node (ref "JP6") (pin "NC") (pinfunction "NC_NC") (pintype "passive"))
      (node (ref "R62") (pin "2") (pinfunction "2_2") (pintype "passive"))
      (node (ref "X2") (pin "13") (pinfunction "1_13") (pintype "passive"))
    )
    (net (code "3") (name "+5V_ISO") (class "Default")
      (node (ref "C23") (pin "1") (pinfunction "1_1") (pintype "passive"))
      (node (ref "C24") (pin "1") (pinfunction "1_1") (pintype "passive"))
      (node (ref "C3") (pin "1") (pinfunction "1_1") (pintype "passive"))
      (node (ref "C8") (pin "1") (pinfunction "1_1") (pintype "passive"))
      (node (ref "IC10") (pin "1") (pinfunction "~{SHDN}_1") (pintype "input"))
      (node (ref "IC10") (pin "2") (pinfunction "VIN_2") (pintype "input"))
      (node (ref "IC11") (pin "5") (pinfunction "V+_5") (pintype "power_in"))
      (node (ref "IC12") (pin "2") (pinfunction "VIN_2") (pintype "passive"))
      (node (ref "IC2") (pin "12") (pinfunction "VL_12") (pintype "power_in"))
      (node (ref "IC5") (pin "12") (pinfunction "VL_12") (pintype "power_in"))
      (node (ref "IC7") (pin "12") (pinfunction "VL_12") (pintype "power_in"))
      (node (ref "IC9") (pin "12") (pinfunction "VL_12") (pintype "power_in"))
      (node (ref "ISEL10A_1") (pin "A3") (pinfunction "COM_A3") (pintype "passive"))
      (node (ref "ISEL10A_2") (pin "A3") (pinfunction "COM_A3") (pintype "passive"))
      (node (ref "ISEL1A_1") (pin "1") (pinfunction "S+_1") (pintype "passive"))
      (node (ref "ISEL1A_1") (pin "6") (pinfunction "R+_6") (pintype "passive"))
      (node (ref "ISEL1A_2") (pin "1") (pinfunction "S+_1") (pintype "passive"))
      (node (ref "ISEL1A_2") (pin "6") (pinfunction "R+_6") (pintype "passive"))
      (node (ref "L3") (pin "P$2") (pinfunction "2_P$2") (pintype "passive"))
      (node (ref "X2") (pin "16") (pinfunction "1_16") (pintype "passive"))
      (node (ref "ZD1") (pin "A") (pinfunction "A_A") (pintype "passive"))
    )
    (net (code "4") (name "+15V_ISO") (class "Default")
      (node (ref "IC2") (pin "13") (pinfunction "V+_13") (pintype "power_in"))
      (node (ref "IC5") (pin "13") (pinfunction "V+_13") (pintype "power_in"))
      (node (ref "IC7") (pin "13") (pinfunction "V+_13") (pintype "power_in"))
      (node (ref "IC9") (pin "13") (pinfunction "V+_13") (pintype "power_in"))
      (node (ref "X2") (pin "20") (pinfunction "1_20") (pintype "passive"))
    )
    (net (code "5") (name "-2V5_ISO") (class "Default")
      (node (ref "C10") (pin "2") (pinfunction "2_2") (pintype "passive"))
      (node (ref "C2") (pin "2") (pinfunction "2_2") (pintype "passive"))
      (node (ref "C24") (pin "2") (pinfunction "2_2") (pintype "passive"))
      (node (ref "C25") (pin "2") (pinfunction "2_2") (pintype "passive"))
      (node (ref "C26") (pin "2") (pinfunction "2_2") (pintype "passive"))
      (node (ref "C27") (pin "2") (pinfunction "2_2") (pintype "passive"))
      (node (ref "C28") (pin "-") (pinfunction "-_-") (pintype "passive"))
      (node (ref "C28A") (pin "2") (pinfunction "2_2") (pintype "passive"))
      (node (ref "C37") (pin "2") (pinfunction "2_2") (pintype "passive"))
      (node (ref "C6") (pin "2") (pinfunction "2_2") (pintype "passive"))
      (node (ref "C7") (pin "2") (pinfunction "2_2") (pintype "passive"))
      (node (ref "IC1") (pin "11") (pinfunction "V-_11") (pintype "power_in"))
      (node (ref "IC10") (pin "3") (pinfunction "GND_3") (pintype "power_in"))
      (node (ref "IC10") (pin "4") (pinfunction "GND_4") (pintype "power_in"))
      (node (ref "IC10") (pin "5") (pinfunction "GND_5") (pintype "power_in"))
      (node (ref "IC10") (pin "8") (pinfunction "GND_8") (pintype "power_in"))
      (node (ref "IC12") (pin "4") (pinfunction "GND_4") (pintype "passive"))
      (node (ref "IC15") (pin "5") (pinfunction "OUT_5") (pintype "passive"))
      (node (ref "IC4") (pin "11") (pinfunction "V-_11") (pintype "power_in"))
      (node (ref "IC6") (pin "2") (pinfunction "V-_2") (pintype "power_in"))
      (node (ref "IC8") (pin "2") (pinfunction "V-_2") (pintype "power_in"))
      (node (ref "R10") (pin "2") (pinfunction "2_2") (pintype "passive"))
      (node (ref "R65") (pin "2") (pinfunction "2_2") (pintype "passive"))
    )
    (net (code "6") (name "-5V_ISO") (class "Default")
      (node (ref "C29") (pin "2") (pinfunction "2_2") (pintype "passive"))
      (node (ref "IC11") (pin "2") (pinfunction "V-_2") (pintype "power_in"))
      (node (ref "L4") (pin "P$2") (pinfunction "2_P$2") (pintype "passive"))
      (node (ref "X2") (pin "15") (pinfunction "1_15") (pintype "passive"))
    )
    (net (code "7") (name "-15V_ISO") (class "Default")
      (node (ref "IC2") (pin "4") (pinfunction "V-_4") (pintype "power_in"))
      (node (ref "IC5") (pin "4") (pinfunction "V-_4") (pintype "power_in"))
      (node (ref "IC7") (pin "4") (pinfunction "V-_4") (pintype "power_in"))
      (node (ref "IC9") (pin "4") (pinfunction "V-_4") (pintype "power_in"))
      (node (ref "X2") (pin "19") (pinfunction "1_19") (pintype "passive"))
    )
    (net (code "8") (name "ADC_CLK") (class "Default")
      (node (ref "JP7") (pin "1") (pinfunction "1_1") (pintype "passive"))
      (node (ref "X2") (pin "4") (pinfunction "1_4") (pintype "passive"))
    )
    (net (code "9") (name "ADC_MISO") (class "Default")
      (node (ref "IC13") (pin "43") (pinfunction "DOUT_43") (pintype "output"))
      (node (ref "X2") (pin "8") (pinfunction "1_8") (pintype "passive"))
    )
    (net (code "10") (name "ADC_MOSI") (class "Default")
      (node (ref "IC13") (pin "34") (pinfunction "DIN_34") (pintype "input"))
      (node (ref "X2") (pin "3") (pinfunction "1_3") (pintype "passive"))
    )
    (net (code "11") (name "ADC_SCK") (class "Default")
      (node (ref "IC13") (pin "40") (pinfunction "SCLK_40") (pintype "input"))
      (node (ref "X2") (pin "6") (pinfunction "1_6") (pintype "passive"))
    )
    (net (code "12") (name "ADC_START") (class "Default")
      (node (ref "IC13") (pin "38") (pinfunction "START_38") (pintype "input"))
      (node (ref "X2") (pin "10") (pinfunction "1_10") (pintype "passive"))
    )
    (net (code "13") (name "AFE_CLK") (class "Default")
      (node (ref "X2") (pin "14") (pinfunction "1_14") (pintype "passive"))
    )
    (net (code "14") (name "AIN1P") (class "Default")
      (node (ref "L1") (pin "P$2") (pinfunction "2_P$2") (pintype "passive"))
      (node (ref "OK1") (pin "4") (pinfunction "S1_4") (pintype "passive"))
      (node (ref "X1") (pin "1") (pinfunction "1_1") (pintype "passive"))
    )
    (net (code "15") (name "AIN2P") (class "Default")
      (node (ref "L2") (pin "P$2") (pinfunction "2_P$2") (pintype "passive"))
      (node (ref "OK3") (pin "4") (pinfunction "S1_4") (pintype "passive"))
      (node (ref "X1") (pin "3") (pinfunction "1_3") (pintype "passive"))
    )
    (net (code "16") (name "AIN3N") (class "Default")
      (node (ref "D11") (pin "2") (pinfunction "A_2") (pintype "passive"))
      (node (ref "D12") (pin "1") (pinfunction "C_1") (pintype "passive"))
      (node (ref "D7") (pin "2") (pinfunction "A_2") (pintype "passive"))
      (node (ref "D8") (pin "1") (pinfunction "C_1") (pintype "passive"))
      (node (ref "JP3") (pin "1") (pinfunction "1_1") (pintype "passive"))
      (node (ref "R32") (pin "2") (pinfunction "2_2") (pintype "passive"))
      (node (ref "R36") (pin "1") (pinfunction "1_1") (pintype "passive"))
      (node (ref "TVS1") (pin "C1") (pinfunction "1_C1") (pintype "passive"))
      (node (ref "X1") (pin "6") (pinfunction "1_6") (pintype "passive"))
    )
    (net (code "17") (name "AIN3P") (class "Default")
      (node (ref "F3") (pin "2") (pinfunction "2_2") (pintype "passive"))
      (node (ref "X1") (pin "5") (pinfunction "1_5") (pintype "passive"))
    )
    (net (code "18") (name "AIN4N") (class "Default")
      (node (ref "D14") (pin "2") (pinfunction "A_2") (pintype "passive"))
      (node (ref "D15") (pin "1") (pinfunction "C_1") (pintype "passive"))
      (node (ref "D18") (pin "2") (pinfunction "A_2") (pintype "passive"))
      (node (ref "D19") (pin "1") (pinfunction "C_1") (pintype "passive"))
      (node (ref "JP4") (pin "1") (pinfunction "1_1") (pintype "passive"))
      (node (ref "R42") (pin "2") (pinfunction "2_2") (pintype "passive"))
      (node (ref "R46") (pin "1") (pinfunction "1_1") (pintype "passive"))
      (node (ref "TVS2") (pin "C1") (pinfunction "1_C1") (pintype "passive"))
      (node (ref "X1") (pin "8") (pinfunction "1_8") (pintype "passive"))
    )
    (net (code "19") (name "AIN4P") (class "Default")
      (node (ref "F5") (pin "1") (pinfunction "1_1") (pintype "passive"))
      (node (ref "X1") (pin "7") (pinfunction "1_7") (pintype "passive"))
    )
    (net (code "20") (name "AIN_U3") (class "Default")
      (node (ref "ISEL1A_1") (pin "10") (pinfunction "NC_10") (pintype "passive"))
      (node (ref "ISEL1A_1") (pin "3") (pinfunction "NC_3") (pintype "passive"))
      (node (ref "R37") (pin "2") (pinfunction "2_2") (pintype "passive"))
      (node (ref "R38") (pin "2") (pinfunction "2_2") (pintype "passive"))
      (node (ref "TVS1") (pin "C2") (pinfunction "2_C2") (pintype "passive"))
      (node (ref "X2") (pin "26") (pinfunction "1_26") (pintype "passive"))
    )
    (net (code "21") (name "AIN_U4") (class "Default")
      (node (ref "ISEL1A_2") (pin "10") (pinfunction "NC_10") (pintype "passive"))
      (node (ref "ISEL1A_2") (pin "3") (pinfunction "NC_3") (pintype "passive"))
      (node (ref "R47") (pin "2") (pinfunction "2_2") (pintype "passive"))
      (node (ref "R48") (pin "2") (pinfunction "2_2") (pintype "passive"))
      (node (ref "TVS2") (pin "C2") (pinfunction "2_C2") (pintype "passive"))
      (node (ref "X2") (pin "24") (pinfunction "1_24") (pintype "passive"))
    )
    (net (code "22") (name "AVSS") (class "Default")
      (node (ref "C11") (pin "1") (pinfunction "1_1") (pintype "passive"))
      (node (ref "C13") (pin "1") (pinfunction "1_1") (pintype "passive"))
      (node (ref "C14") (pin "2") (pinfunction "2_2") (pintype "passive"))
      (node (ref "C15") (pin "1") (pinfunction "1_1") (pintype "passive"))
      (node (ref "C16") (pin "2") (pinfunction "2_2") (pintype "passive"))
      (node (ref "C21") (pin "1") (pinfunction "1_1") (pintype "passive"))
      (node (ref "C22") (pin "2") (pinfunction "2_2") (pintype "passive"))
      (node (ref "C42") (pin "1") (pinfunction "1_1") (pintype "passive"))
      (node (ref "C43") (pin "2") (pinfunction "2_2") (pintype "passive"))
      (node (ref "C46") (pin "2") (pinfunction "2_2") (pintype "passive"))
      (node (ref "C47") (pin "1") (pinfunction "1_1") (pintype "passive"))
      (node (ref "C51") (pin "1") (pinfunction "1_1") (pintype "passive"))
      (node (ref "C52") (pin "1") (pinfunction "1_1") (pintype "passive"))
      (node (ref "IC13") (pin "20") (pinfunction "AVSS_2_20") (pintype "power_in"))
      (node (ref "IC13") (pin "23") (pinfunction "AVSS_3_23") (pintype "power_in"))
      (node (ref "IC13") (pin "25") (pinfunction "VREFN_25") (pintype "input"))
      (node (ref "IC13") (pin "32") (pinfunction "AVSS_4_32") (pintype "power_in"))
      (node (ref "IC13") (pin "53") (pinfunction "AVSS1_53") (pintype "power_in"))
      (node (ref "IC13") (pin "57") (pinfunction "AVSS_5_57") (pintype "power_in"))
      (node (ref "IC13") (pin "58") (pinfunction "AVSS_58") (pintype "power_in"))
      (node (ref "R65") (pin "1") (pinfunction "1_1") (pintype "passive"))
    )
    (net (code "23") (name "GND") (class "Default")
      (node (ref "C1") (pin "1") (pinfunction "1_1") (pintype "passive"))
      (node (ref "C10") (pin "1") (pinfunction "1_1") (pintype "passive"))
      (node (ref "C17") (pin "1") (pinfunction "1_1") (pintype "passive"))
      (node (ref "C18") (pin "1") (pinfunction "1_1") (pintype "passive"))
      (node (ref "C19") (pin "1") (pinfunction "1_1") (pintype "passive"))
      (node (ref "C2") (pin "1") (pinfunction "1_1") (pintype "passive"))
      (node (ref "C20") (pin "1") (pinfunction "1_1") (pintype "passive"))
      (node (ref "C23") (pin "2") (pinfunction "2_2") (pintype "passive"))
      (node (ref "C29") (pin "1") (pinfunction "1_1") (pintype "passive"))
      (node (ref "C3") (pin "2") (pinfunction "2_2") (pintype "passive"))
      (node (ref "C34") (pin "2") (pinfunction "2_2") (pintype "passive"))
      (node (ref "C35") (pin "2") (pinfunction "2_2") (pintype "passive"))
      (node (ref "C36") (pin "1") (pinfunction "1_1") (pintype "passive"))
      (node (ref "C37") (pin "1") (pinfunction "1_1") (pintype "passive"))
      (node (ref "C38") (pin "1") (pinfunction "1_1") (pintype "passive"))
      (node (ref "C39") (pin "1") (pinfunction "1_1") (pintype "passive"))
      (node (ref "C4") (pin "1") (pinfunction "1_1") (pintype "passive"))
      (node (ref "C40") (pin "1") (pinfunction "1_1") (pintype "passive"))
      (node (ref "C41") (pin "1") (pinfunction "1_1") (pintype "passive"))
      (node (ref "C44") (pin "2") (pinfunction "2_2") (pintype "passive"))
      (node (ref "C45") (pin "2") (pinfunction "2_2") (pintype "passive"))
      (node (ref "C48") (pin "2") (pinfunction "2_2") (pintype "passive"))
      (node (ref "C49") (pin "1") (pinfunction "1_1") (pintype "passive"))
      (node (ref "C5") (pin "1") (pinfunction "1_1") (pintype "passive"))
      (node (ref "C50") (pin "1") (pinfunction "1_1") (pintype "passive"))
      (node (ref "C51") (pin "2") (pinfunction "2_2") (pintype "passive"))
      (node (ref "C52") (pin "2") (pinfunction "2_2") (pintype "passive"))
      (node (ref "C6") (pin "1") (pinfunction "1_1") (pintype "passive"))
      (node (ref "C7") (pin "1") (pinfunction "1_1") (pintype "passive"))
      (node (ref "C8") (pin "2") (pinfunction "2_2") (pintype "passive"))
      (node (ref "C9") (pin "1") (pinfunction "1_1") (pintype "passive"))
      (node (ref "D14") (pin "1") (pinfunction "C_1") (pintype "passive"))
      (node (ref "D15") (pin "2") (pinfunction "A_2") (pintype "passive"))
      (node (ref "D2") (pin "1") (pinfunction "C_1") (pintype "passive"))
      (node (ref "D3") (pin "2") (pinfunction "A_2") (pintype "passive"))
      (node (ref "D5") (pin "1") (pinfunction "C_1") (pintype "passive"))
      (node (ref "D6") (pin "2") (pinfunction "A_2") (pintype "passive"))
      (node (ref "D7") (pin "1") (pinfunction "C_1") (pintype "passive"))
      (node (ref "D8") (pin "2") (pinfunction "A_2") (pintype "passive"))
      (node (ref "GND") (pin "1") (pinfunction "P$1_1") (pintype "bidirectional"))
      (node (ref "IC13") (pin "31") (pinfunction "RESV1_31") (pintype "input"))
      (node (ref "IC13") (pin "33") (pinfunction "DGND_2_33") (pintype "power_in"))
      (node (ref "IC13") (pin "41") (pinfunction "DAISY_IN_41") (pintype "input"))
      (node (ref "IC13") (pin "49") (pinfunction "DGND_3_49") (pintype "power_in"))
      (node (ref "IC13") (pin "51") (pinfunction "DGND_51") (pintype "power_in"))
      (node (ref "IC14") (pin "2") (pinfunction "GND_2") (pintype "passive"))
      (node (ref "IC15") (pin "1") (pinfunction "GND_1") (pintype "passive"))
      (node (ref "IC2") (pin "5") (pinfunction "GND_5") (pintype "power_in"))
      (node (ref "IC3") (pin "9") (pinfunction "GND_9") (pintype "input"))
      (node (ref "IC5") (pin "5") (pinfunction "GND_5") (pintype "power_in"))
      (node (ref "IC7") (pin "5") (pinfunction "GND_5") (pintype "power_in"))
      (node (ref "IC9") (pin "5") (pinfunction "GND_5") (pintype "power_in"))
      (node (ref "JP1") (pin "2") (pinfunction "2_2") (pintype "passive"))
      (node (ref "JP2") (pin "2") (pinfunction "2_2") (pintype "passive"))
      (node (ref "JP3") (pin "2") (pinfunction "2_2") (pintype "passive"))
      (node (ref "JP4") (pin "2") (pinfunction "2_2") (pintype "passive"))
      (node (ref "JP6") (pin "NO") (pinfunction "NO_NO") (pintype "passive"))
      (node (ref "OK1") (pin "2") (pinfunction "C_2") (pintype "passive"))
      (node (ref "OK2") (pin "2") (pinfunction "C_2") (pintype "passive"))
      (node (ref "OK3") (pin "2") (pinfunction "C_2") (pintype "passive"))
      (node (ref "OK4") (pin "2") (pinfunction "C_2") (pintype "passive"))
      (node (ref "R11") (pin "1") (pinfunction "1_1") (pintype "passive"))
      (node (ref "R24") (pin "1") (pinfunction "1_1") (pintype "passive"))
      (node (ref "R32") (pin "1") (pinfunction "1_1") (pintype "passive"))
      (node (ref "R42") (pin "1") (pinfunction "1_1") (pintype "passive"))
      (node (ref "R5") (pin "2") (pinfunction "2_2") (pintype "passive"))
      (node (ref "R7") (pin "1") (pinfunction "1_1") (pintype "passive"))
      (node (ref "S1") (pin "SH.1") (pinfunction "SH_SH.1") (pintype "passive"))
      (node (ref "S1") (pin "SH.2") (pinfunction "SH_SH.2") (pintype "passive"))
      (node (ref "S1") (pin "SH.3") (pinfunction "SH_SH.3") (pintype "passive"))
      (node (ref "S1") (pin "SH.4") (pinfunction "SH_SH.4") (pintype "passive"))
      (node (ref "S1") (pin "SH.5") (pinfunction "SH_SH.5") (pintype "passive"))
      (node (ref "S1") (pin "SH.6") (pinfunction "SH_SH.6") (pintype "passive"))
      (node (ref "S1") (pin "SH.7") (pinfunction "SH_SH.7") (pintype "passive"))
      (node (ref "S1") (pin "SH.8") (pinfunction "SH_SH.8") (pintype "passive"))
      (node (ref "X2") (pin "1") (pinfunction "1_1") (pintype "passive"))
      (node (ref "X2") (pin "11") (pinfunction "1_11") (pintype "passive"))
      (node (ref "X2") (pin "12") (pinfunction "1_12") (pintype "passive"))
      (node (ref "X2") (pin "2") (pinfunction "1_2") (pintype "passive"))
      (node (ref "X2") (pin "21") (pinfunction "1_21") (pintype "passive"))
      (node (ref "X2") (pin "22") (pinfunction "1_22") (pintype "passive"))
      (node (ref "X2") (pin "27") (pinfunction "1_27") (pintype "passive"))
      (node (ref "X2") (pin "28") (pinfunction "1_28") (pintype "passive"))
      (node (ref "X3") (pin "1") (pinfunction "1_1") (pintype "passive"))
      (node (ref "X3") (pin "2") (pinfunction "1_2") (pintype "passive"))
      (node (ref "X3") (pin "27") (pinfunction "1_27") (pintype "passive"))
      (node (ref "X3") (pin "28") (pinfunction "1_28") (pintype "passive"))
    )
    (net (code "24") (name "HI_CLAMP") (class "Default")
      (node (ref "IC1") (pin "12") (pinfunction "+IN_12") (pintype "input"))
      (node (ref "IC1") (pin "3") (pinfunction "+IN_3") (pintype "input"))
      (node (ref "IC4") (pin "12") (pinfunction "+IN_12") (pintype "input"))
      (node (ref "IC4") (pin "3") (pinfunction "+IN_3") (pintype "input"))
      (node (ref "R2") (pin "2") (pinfunction "2_2") (pintype "passive"))
      (node (ref "R5") (pin "1") (pinfunction "1_1") (pintype "passive"))
    )
    (net (code "25") (name "IN1N") (class "Default")
      (node (ref "D2") (pin "2") (pinfunction "A_2") (pintype "passive"))
      (node (ref "D3") (pin "1") (pinfunction "C_1") (pintype "passive"))
      (node (ref "JP1") (pin "1") (pinfunction "1_1") (pintype "passive"))
      (node (ref "R11") (pin "2") (pinfunction "2_2") (pintype "passive"))
      (node (ref "R17") (pin "1") (pinfunction "1_1") (pintype "passive"))
      (node (ref "R4") (pin "1") (pinfunction "1_1") (pintype "passive"))
      (node (ref "R55") (pin "1") (pinfunction "1_1") (pintype "passive"))
      (node (ref "X1") (pin "2") (pinfunction "1_2") (pintype "passive"))
    )
    (net (code "26") (name "IN1P") (class "Default")
      (node (ref "D1") (pin "3") (pinfunction "AC_3") (pintype "passive"))
      (node (ref "IC1") (pin "13") (pinfunction "-IN_13") (pintype "input"))
      (node (ref "IC1") (pin "9") (pinfunction "-IN_9") (pintype "input"))
      (node (ref "IC2") (pin "10") (pinfunction "D_10") (pintype "bidirectional"))
      (node (ref "IC2") (pin "15") (pinfunction "D_15") (pintype "bidirectional"))
      (node (ref "IC2") (pin "2") (pinfunction "D_2") (pintype "bidirectional"))
      (node (ref "IC2") (pin "7") (pinfunction "D_7") (pintype "bidirectional"))
      (node (ref "R54") (pin "1") (pinfunction "1_1") (pintype "passive"))
    )
    (net (code "27") (name "IN2N") (class "Default")
      (node (ref "D5") (pin "2") (pinfunction "A_2") (pintype "passive"))
      (node (ref "D6") (pin "1") (pinfunction "C_1") (pintype "passive"))
      (node (ref "JP2") (pin "1") (pinfunction "1_1") (pintype "passive"))
      (node (ref "R20") (pin "1") (pinfunction "1_1") (pintype "passive"))
      (node (ref "R24") (pin "2") (pinfunction "2_2") (pintype "passive"))
      (node (ref "R30") (pin "1") (pinfunction "1_1") (pintype "passive"))
      (node (ref "R57") (pin "1") (pinfunction "1_1") (pintype "passive"))
      (node (ref "X1") (pin "4") (pinfunction "1_4") (pintype "passive"))
    )
    (net (code "28") (name "IN2P") (class "Default")
      (node (ref "D4") (pin "3") (pinfunction "AC_3") (pintype "passive"))
      (node (ref "IC4") (pin "13") (pinfunction "-IN_13") (pintype "input"))
      (node (ref "IC4") (pin "9") (pinfunction "-IN_9") (pintype "input"))
      (node (ref "IC5") (pin "10") (pinfunction "D_10") (pintype "bidirectional"))
      (node (ref "IC5") (pin "15") (pinfunction "D_15") (pintype "bidirectional"))
      (node (ref "IC5") (pin "2") (pinfunction "D_2") (pintype "bidirectional"))
      (node (ref "IC5") (pin "7") (pinfunction "D_7") (pintype "bidirectional"))
      (node (ref "R56") (pin "1") (pinfunction "1_1") (pintype "passive"))
    )
    (net (code "29") (name "IN3N") (class "Default")
      (node (ref "R36") (pin "1S") (pinfunction "1S_1S") (pintype "passive"))
      (node (ref "R40") (pin "1") (pinfunction "1_1") (pintype "passive"))
      (node (ref "R59") (pin "1") (pinfunction "1_1") (pintype "passive"))
      (node (ref "X2") (pin "25") (pinfunction "1_25") (pintype "passive"))
    )
    (net (code "30") (name "IN3P") (class "Default")
      (node (ref "D13") (pin "3") (pinfunction "AC_3") (pintype "passive"))
      (node (ref "IC4") (pin "2") (pinfunction "-IN_2") (pintype "input"))
      (node (ref "IC4") (pin "6") (pinfunction "-IN_6") (pintype "input"))
      (node (ref "IC7") (pin "11") (pinfunction "S_11") (pintype "bidirectional"))
      (node (ref "IC7") (pin "15") (pinfunction "D_15") (pintype "bidirectional"))
      (node (ref "IC7") (pin "3") (pinfunction "S_3") (pintype "bidirectional"))
      (node (ref "IC7") (pin "7") (pinfunction "D_7") (pintype "bidirectional"))
      (node (ref "R58") (pin "1") (pinfunction "1_1") (pintype "passive"))
    )
    (net (code "31") (name "IN4N") (class "Default")
      (node (ref "R46") (pin "1S") (pinfunction "1S_1S") (pintype "passive"))
      (node (ref "R50") (pin "1") (pinfunction "1_1") (pintype "passive"))
      (node (ref "R61") (pin "1") (pinfunction "1_1") (pintype "passive"))
      (node (ref "X2") (pin "23") (pinfunction "1_23") (pintype "passive"))
    )
    (net (code "32") (name "IN4P") (class "Default")
      (node (ref "D20") (pin "3") (pinfunction "AC_3") (pintype "passive"))
      (node (ref "IC1") (pin "2") (pinfunction "-IN_2") (pintype "input"))
      (node (ref "IC1") (pin "6") (pinfunction "-IN_6") (pintype "input"))
      (node (ref "IC9") (pin "11") (pinfunction "S_11") (pintype "bidirectional"))
      (node (ref "IC9") (pin "15") (pinfunction "D_15") (pintype "bidirectional"))
      (node (ref "IC9") (pin "3") (pinfunction "S_3") (pintype "bidirectional"))
      (node (ref "IC9") (pin "7") (pinfunction "D_7") (pintype "bidirectional"))
      (node (ref "R60") (pin "1") (pinfunction "1_1") (pintype "passive"))
    )
    (net (code "33") (name "ISEL#1") (class "Default")
      (node (ref "IC2") (pin "9") (pinfunction "IN_9") (pintype "input"))
      (node (ref "R3") (pin "2") (pinfunction "2_2") (pintype "passive"))
      (node (ref "X3") (pin "3") (pinfunction "1_3") (pintype "passive"))
    )
    (net (code "34") (name "ISEL#2") (class "Default")
      (node (ref "IC5") (pin "9") (pinfunction "IN_9") (pintype "input"))
      (node (ref "R19") (pin "2") (pinfunction "2_2") (pintype "passive"))
      (node (ref "X3") (pin "4") (pinfunction "1_4") (pintype "passive"))
    )
    (net (code "35") (name "ISEL10A_R3_OUT") (class "Default")
      (node (ref "IC3") (pin "15") (pinfunction "4C_15") (pintype "output"))
      (node (ref "ISEL10A_1") (pin "A1") (pinfunction "R_A1") (pintype "passive"))
    )
    (net (code "36") (name "ISEL10A_R4_OUT") (class "Default")
      (node (ref "IC3") (pin "11") (pinfunction "8C_11") (pintype "output"))
      (node (ref "ISEL10A_2") (pin "A1") (pinfunction "R_A1") (pintype "passive"))
    )
    (net (code "37") (name "ISEL10A_S3_OUT") (class "Default")
      (node (ref "IC3") (pin "16") (pinfunction "3C_16") (pintype "output"))
      (node (ref "ISEL10A_1") (pin "A2") (pinfunction "S_A2") (pintype "passive"))
    )
    (net (code "38") (name "ISEL10A_S4_OUT") (class "Default")
      (node (ref "IC3") (pin "12") (pinfunction "7C_12") (pintype "output"))
      (node (ref "ISEL10A_2") (pin "A2") (pinfunction "S_A2") (pintype "passive"))
    )
    (net (code "39") (name "ISEL10_R#3") (class "Default")
      (node (ref "IC3") (pin "4") (pinfunction "4B_4") (pintype "input"))
      (node (ref "X3") (pin "21") (pinfunction "1_21") (pintype "passive"))
    )
    (net (code "40") (name "ISEL10_R#4") (class "Default")
      (node (ref "IC3") (pin "8") (pinfunction "8B_8") (pintype "input"))
      (node (ref "X3") (pin "22") (pinfunction "1_22") (pintype "passive"))
    )
    (net (code "41") (name "ISEL10_S#3") (class "Default")
      (node (ref "IC3") (pin "3") (pinfunction "3B_3") (pintype "input"))
      (node (ref "X3") (pin "19") (pinfunction "1_19") (pintype "passive"))
    )
    (net (code "42") (name "ISEL10_S#4") (class "Default")
      (node (ref "IC3") (pin "7") (pinfunction "7B_7") (pintype "input"))
      (node (ref "X3") (pin "20") (pinfunction "1_20") (pintype "passive"))
    )
    (net (code "43") (name "ISEL_LOW#3") (class "Default")
      (node (ref "IC7") (pin "16") (pinfunction "IN_16") (pintype "input"))
      (node (ref "X3") (pin "23") (pinfunction "1_23") (pintype "passive"))
    )
    (net (code "44") (name "ISEL_LOW#4") (class "Default")
      (node (ref "IC9") (pin "16") (pinfunction "IN_16") (pintype "input"))
      (node (ref "X3") (pin "24") (pinfunction "1_24") (pintype "passive"))
    )
    (net (code "45") (name "ISEL_MID#3") (class "Default")
      (node (ref "IC7") (pin "9") (pinfunction "IN_9") (pintype "input"))
      (node (ref "Q5") (pin "1") (pinfunction "G_1") (pintype "passive"))
      (node (ref "Q6") (pin "1") (pinfunction "G_1") (pintype "passive"))
      (node (ref "X3") (pin "25") (pinfunction "1_25") (pintype "passive"))
    )
    (net (code "46") (name "ISEL_MID#4") (class "Default")
      (node (ref "IC9") (pin "9") (pinfunction "IN_9") (pintype "input"))
      (node (ref "Q7") (pin "1") (pinfunction "G_1") (pintype "passive"))
      (node (ref "Q8") (pin "1") (pinfunction "G_1") (pintype "passive"))
      (node (ref "X3") (pin "26") (pinfunction "1_26") (pintype "passive"))
    )
    (net (code "47") (name "ISEL_R#3") (class "Default")
      (node (ref "IC3") (pin "2") (pinfunction "2B_2") (pintype "input"))
      (node (ref "X3") (pin "17") (pinfunction "1_17") (pintype "passive"))
    )
    (net (code "48") (name "ISEL_R#4") (class "Default")
      (node (ref "IC3") (pin "6") (pinfunction "6B_6") (pintype "input"))
      (node (ref "X3") (pin "18") (pinfunction "1_18") (pintype "passive"))
    )
    (net (code "49") (name "ISEL_R3_OUT") (class "Default")
      (node (ref "IC3") (pin "17") (pinfunction "2C_17") (pintype "output"))
      (node (ref "ISEL1A_1") (pin "7") (pinfunction "R-_7") (pintype "passive"))
    )
    (net (code "50") (name "ISEL_R4_OUT") (class "Default")
      (node (ref "IC3") (pin "13") (pinfunction "6C_13") (pintype "output"))
      (node (ref "ISEL1A_2") (pin "7") (pinfunction "R-_7") (pintype "passive"))
    )
    (net (code "51") (name "ISEL_S#3") (class "Default")
      (node (ref "IC3") (pin "1") (pinfunction "1B_1") (pintype "input"))
      (node (ref "X3") (pin "15") (pinfunction "1_15") (pintype "passive"))
    )
    (net (code "52") (name "ISEL_S#4") (class "Default")
      (node (ref "IC3") (pin "5") (pinfunction "5B_5") (pintype "input"))
      (node (ref "X3") (pin "16") (pinfunction "1_16") (pintype "passive"))
    )
    (net (code "53") (name "ISEL_S3_OUT") (class "Default")
      (node (ref "IC3") (pin "18") (pinfunction "1C_18") (pintype "output"))
      (node (ref "ISEL1A_1") (pin "12") (pinfunction "S-_12") (pintype "passive"))
    )
    (net (code "54") (name "ISEL_S4_OUT") (class "Default")
      (node (ref "IC3") (pin "14") (pinfunction "5C_14") (pintype "output"))
      (node (ref "ISEL1A_2") (pin "12") (pinfunction "S-_12") (pintype "passive"))
    )
    (net (code "55") (name "LO_CLAMP") (class "Default")
      (node (ref "IC1") (pin "10") (pinfunction "+IN_10") (pintype "input"))
      (node (ref "IC1") (pin "5") (pinfunction "+IN_5") (pintype "input"))
      (node (ref "IC4") (pin "10") (pinfunction "+IN_10") (pintype "input"))
      (node (ref "IC4") (pin "5") (pinfunction "+IN_5") (pintype "input"))
      (node (ref "R10") (pin "1") (pinfunction "1_1") (pintype "passive"))
      (node (ref "R7") (pin "2") (pinfunction "2_2") (pintype "passive"))
    )
    (net (code "56") (name "Net-(D1-A)") (class "Default")
      (node (ref "D1") (pin "1") (pinfunction "A_1") (pintype "passive"))
      (node (ref "IC1") (pin "8") (pinfunction "OUT_8") (pintype "output"))
    )
    (net (code "57") (name "Net-(D1-C)") (class "Default")
      (node (ref "D1") (pin "2") (pinfunction "C_2") (pintype "passive"))
      (node (ref "IC1") (pin "14") (pinfunction "OUT_14") (pintype "output"))
    )
    (net (code "58") (name "Net-(D4-A)") (class "Default")
      (node (ref "D4") (pin "1") (pinfunction "A_1") (pintype "passive"))
      (node (ref "IC4") (pin "8") (pinfunction "OUT_8") (pintype "output"))
    )
    (net (code "59") (name "Net-(D4-C)") (class "Default")
      (node (ref "D4") (pin "2") (pinfunction "C_2") (pintype "passive"))
      (node (ref "IC4") (pin "14") (pinfunction "OUT_14") (pintype "output"))
    )
    (net (code "60") (name "Net-(D10-A)") (class "Default")
      (node (ref "D10") (pin "2") (pinfunction "A_2") (pintype "passive"))
      (node (ref "D11") (pin "1") (pinfunction "C_1") (pintype "passive"))
      (node (ref "D12") (pin "2") (pinfunction "A_2") (pintype "passive"))
      (node (ref "D9") (pin "1") (pinfunction "C_1") (pintype "passive"))
      (node (ref "R35") (pin "2") (pinfunction "2_2") (pintype "passive"))
    )
    (net (code "61") (name "Net-(D10-C)") (class "Default")
      (node (ref "D10") (pin "1") (pinfunction "C_1") (pintype "passive"))
      (node (ref "D9") (pin "2") (pinfunction "A_2") (pintype "passive"))
      (node (ref "IC7") (pin "14") (pinfunction "S_14") (pintype "bidirectional"))
      (node (ref "ISEL1A_1") (pin "5") (pinfunction "NO_5") (pintype "passive"))
      (node (ref "ISEL1A_1") (pin "8") (pinfunction "NO_8") (pintype "passive"))
      (node (ref "Q5") (pin "2") (pinfunction "S_2") (pintype "passive"))
      (node (ref "R31") (pin "2") (pinfunction "2_2") (pintype "passive"))
      (node (ref "R34") (pin "2") (pinfunction "2_2") (pintype "passive"))
    )
    (net (code "62") (name "Net-(D13-A)") (class "Default")
      (node (ref "D13") (pin "1") (pinfunction "A_1") (pintype "passive"))
      (node (ref "IC4") (pin "7") (pinfunction "OUT_7") (pintype "output"))
    )
    (net (code "63") (name "Net-(D13-C)") (class "Default")
      (node (ref "D13") (pin "2") (pinfunction "C_2") (pintype "passive"))
      (node (ref "IC4") (pin "1") (pinfunction "OUT_1") (pintype "output"))
    )
    (net (code "64") (name "Net-(D16-A)") (class "Default")
      (node (ref "D16") (pin "2") (pinfunction "A_2") (pintype "passive"))
      (node (ref "D17") (pin "1") (pinfunction "C_1") (pintype "passive"))
      (node (ref "IC9") (pin "14") (pinfunction "S_14") (pintype "bidirectional"))
      (node (ref "ISEL1A_2") (pin "5") (pinfunction "NO_5") (pintype "passive"))
      (node (ref "ISEL1A_2") (pin "8") (pinfunction "NO_8") (pintype "passive"))
      (node (ref "Q7") (pin "2") (pinfunction "S_2") (pintype "passive"))
      (node (ref "R41") (pin "2") (pinfunction "2_2") (pintype "passive"))
      (node (ref "R44") (pin "2") (pinfunction "2_2") (pintype "passive"))
    )
    (net (code "65") (name "Net-(D16-C)") (class "Default")
      (node (ref "D16") (pin "1") (pinfunction "C_1") (pintype "passive"))
      (node (ref "D17") (pin "2") (pinfunction "A_2") (pintype "passive"))
      (node (ref "D18") (pin "1") (pinfunction "C_1") (pintype "passive"))
      (node (ref "D19") (pin "2") (pinfunction "A_2") (pintype "passive"))
      (node (ref "R45") (pin "2") (pinfunction "2_2") (pintype "passive"))
    )
    (net (code "66") (name "Net-(D20-A)") (class "Default")
      (node (ref "D20") (pin "1") (pinfunction "A_1") (pintype "passive"))
      (node (ref "IC1") (pin "7") (pinfunction "OUT_7") (pintype "output"))
    )
    (net (code "67") (name "Net-(D20-C)") (class "Default")
      (node (ref "D20") (pin "2") (pinfunction "C_2") (pintype "passive"))
      (node (ref "IC1") (pin "1") (pinfunction "OUT_1") (pintype "output"))
    )
    (net (code "68") (name "Net-(F1-P$1)") (class "Default")
      (node (ref "F1") (pin "1") (pinfunction "P$1_1") (pintype "bidirectional"))
      (node (ref "R1") (pin "1") (pinfunction "1_1") (pintype "passive"))
    )
    (net (code "69") (name "Net-(F1-P$2)") (class "Default")
      (node (ref "F1") (pin "2") (pinfunction "P$2_2") (pintype "bidirectional"))
      (node (ref "Q1") (pin "1") (pinfunction "G_1") (pintype "passive"))
      (node (ref "Q2") (pin "3") (pinfunction "S_3") (pintype "passive"))
    )
    (net (code "70") (name "Net-(F2-P$1)") (class "Default")
      (node (ref "F2") (pin "1") (pinfunction "P$1_1") (pintype "bidirectional"))
      (node (ref "R18") (pin "1") (pinfunction "1_1") (pintype "passive"))
    )
    (net (code "71") (name "Net-(F2-P$2)") (class "Default")
      (node (ref "F2") (pin "2") (pinfunction "P$2_2") (pintype "bidirectional"))
      (node (ref "Q3") (pin "1") (pinfunction "G_1") (pintype "passive"))
      (node (ref "Q4") (pin "3") (pinfunction "S_3") (pintype "passive"))
    )
    (net (code "72") (name "Net-(IC2A-S)") (class "Default")
      (node (ref "IC2") (pin "3") (pinfunction "S_3") (pintype "bidirectional"))
      (node (ref "R14") (pin "1") (pinfunction "1_1") (pintype "passive"))
      (node (ref "R15") (pin "2") (pinfunction "2_2") (pintype "passive"))
    )
    (net (code "73") (name "Net-(IC2B-S)") (class "Default")
      (node (ref "IC2") (pin "14") (pinfunction "S_14") (pintype "bidirectional"))
      (node (ref "R16") (pin "1") (pinfunction "1_1") (pintype "passive"))
      (node (ref "R17") (pin "2") (pinfunction "2_2") (pintype "passive"))
    )
    (net (code "74") (name "Net-(IC2C-S)") (class "Default")
      (node (ref "IC2") (pin "11") (pinfunction "S_11") (pintype "bidirectional"))
      (node (ref "Q2") (pin "2") (pinfunction "D_2") (pintype "passive"))
      (node (ref "Q2") (pin "4") (pinfunction "D_4") (pintype "passive"))
      (node (ref "R4") (pin "2") (pinfunction "2_2") (pintype "passive"))
    )
    (net (code "75") (name "Net-(IC2D-S)") (class "Default")
      (node (ref "IC2") (pin "6") (pinfunction "S_6") (pintype "bidirectional"))
      (node (ref "OK2") (pin "4") (pinfunction "S1_4") (pintype "passive"))
    )
    (net (code "76") (name "Net-(IC3-COM)") (class "Default")
      (node (ref "IC3") (pin "10") (pinfunction "COM_10") (pintype "passive"))
      (node (ref "ZD1") (pin "C") (pinfunction "C_C") (pintype "passive"))
    )
    (net (code "77") (name "Net-(IC5A-S)") (class "Default")
      (node (ref "IC5") (pin "3") (pinfunction "S_3") (pintype "bidirectional"))
      (node (ref "R27") (pin "1") (pinfunction "1_1") (pintype "passive"))
      (node (ref "R28") (pin "2") (pinfunction "2_2") (pintype "passive"))
    )
    (net (code "78") (name "Net-(IC5B-S)") (class "Default")
      (node (ref "IC5") (pin "14") (pinfunction "S_14") (pintype "bidirectional"))
      (node (ref "R29") (pin "1") (pinfunction "1_1") (pintype "passive"))
      (node (ref "R30") (pin "2") (pinfunction "2_2") (pintype "passive"))
    )
    (net (code "79") (name "Net-(IC5C-S)") (class "Default")
      (node (ref "IC5") (pin "11") (pinfunction "S_11") (pintype "bidirectional"))
      (node (ref "Q4") (pin "2") (pinfunction "D_2") (pintype "passive"))
      (node (ref "Q4") (pin "4") (pinfunction "D_4") (pintype "passive"))
      (node (ref "R20") (pin "2") (pinfunction "2_2") (pintype "passive"))
    )
    (net (code "80") (name "Net-(IC5D-S)") (class "Default")
      (node (ref "IC5") (pin "6") (pinfunction "S_6") (pintype "bidirectional"))
      (node (ref "OK4") (pin "4") (pinfunction "S1_4") (pintype "passive"))
    )
    (net (code "81") (name "Net-(IC6A-+IN)") (class "Default")
      (node (ref "IC6") (pin "3") (pinfunction "+IN_3") (pintype "input"))
      (node (ref "R34") (pin "1") (pinfunction "1_1") (pintype "passive"))
    )
    (net (code "82") (name "Net-(IC6A--IN)") (class "Default")
      (node (ref "IC6") (pin "1") (pinfunction "OUT_1") (pintype "output"))
      (node (ref "IC6") (pin "4") (pinfunction "-IN_4") (pintype "input"))
      (node (ref "R35") (pin "1") (pinfunction "1_1") (pintype "passive"))
    )
    (net (code "83") (name "Net-(IC7A-D)") (class "Default")
      (node (ref "IC7") (pin "2") (pinfunction "D_2") (pintype "bidirectional"))
      (node (ref "R39") (pin "1") (pinfunction "1_1") (pintype "passive"))
      (node (ref "R40") (pin "2") (pinfunction "2_2") (pintype "passive"))
    )
    (net (code "84") (name "Net-(IC7C-D)") (class "Default")
      (node (ref "IC7") (pin "10") (pinfunction "D_10") (pintype "bidirectional"))
      (node (ref "Q6") (pin "2") (pinfunction "S_2") (pintype "passive"))
      (node (ref "R31") (pin "1") (pinfunction "1_1") (pintype "passive"))
      (node (ref "R33") (pin "2") (pinfunction "2_2") (pintype "passive"))
    )
    (net (code "85") (name "Net-(IC7D-S)") (class "Default")
      (node (ref "IC7") (pin "6") (pinfunction "S_6") (pintype "bidirectional"))
      (node (ref "R37") (pin "1") (pinfunction "1_1") (pintype "passive"))
    )
    (net (code "86") (name "Net-(IC8A-+IN)") (class "Default")
      (node (ref "IC8") (pin "3") (pinfunction "+IN_3") (pintype "input"))
      (node (ref "R44") (pin "1") (pinfunction "1_1") (pintype "passive"))
    )
    (net (code "87") (name "Net-(IC8A--IN)") (class "Default")
      (node (ref "IC8") (pin "1") (pinfunction "OUT_1") (pintype "output"))
      (node (ref "IC8") (pin "4") (pinfunction "-IN_4") (pintype "input"))
      (node (ref "R45") (pin "1") (pinfunction "1_1") (pintype "passive"))
    )
    (net (code "88") (name "Net-(IC9A-D)") (class "Default")
      (node (ref "IC9") (pin "2") (pinfunction "D_2") (pintype "bidirectional"))
      (node (ref "R49") (pin "1") (pinfunction "1_1") (pintype "passive"))
      (node (ref "R50") (pin "2") (pinfunction "2_2") (pintype "passive"))
    )
    (net (code "89") (name "Net-(IC9C-D)") (class "Default")
      (node (ref "IC9") (pin "10") (pinfunction "D_10") (pintype "bidirectional"))
      (node (ref "Q8") (pin "2") (pinfunction "S_2") (pintype "passive"))
      (node (ref "R41") (pin "1") (pinfunction "1_1") (pintype "passive"))
      (node (ref "R43") (pin "2") (pinfunction "2_2") (pintype "passive"))
    )
    (net (code "90") (name "Net-(IC9D-S)") (class "Default")
      (node (ref "IC9") (pin "6") (pinfunction "S_6") (pintype "bidirectional"))
      (node (ref "R47") (pin "1") (pinfunction "1_1") (pintype "passive"))
    )
    (net (code "91") (name "Net-(IC10-VOUT_F)") (class "Default")
      (node (ref "C27") (pin "1") (pinfunction "1_1") (pintype "passive"))
      (node (ref "C28") (pin "+") (pinfunction "+_+") (pintype "passive"))
      (node (ref "C28A") (pin "1") (pinfunction "1_1") (pintype "passive"))
      (node (ref "IC10") (pin "6") (pinfunction "VOUT_S_6") (pintype "output"))
      (node (ref "IC10") (pin "7") (pinfunction "VOUT_F_7") (pintype "output"))
      (node (ref "IC12") (pin "6") (pinfunction "VOUT_6") (pintype "output"))
      (node (ref "JP5") (pin "NC") (pinfunction "NC_NC") (pintype "passive"))
      (node (ref "R53") (pin "2") (pinfunction "2_2") (pintype "passive"))
    )
    (net (code "92") (name "Net-(IC11A-+IN)") (class "Default")
      (node (ref "C25") (pin "1") (pinfunction "1_1") (pintype "passive"))
      (node (ref "C26") (pin "1") (pinfunction "1_1") (pintype "passive"))
      (node (ref "IC11") (pin "3") (pinfunction "+IN_3") (pintype "input"))
      (node (ref "R53") (pin "1") (pinfunction "1_1") (pintype "passive"))
    )
    (net (code "93") (name "Net-(IC11A--IN)") (class "Default")
      (node (ref "C12") (pin "2") (pinfunction "2_2") (pintype "passive"))
      (node (ref "IC11") (pin "4") (pinfunction "-IN_4") (pintype "input"))
      (node (ref "R51") (pin "2") (pinfunction "2_2") (pintype "passive"))
    )
    (net (code "94") (name "Net-(IC11A-OUT)") (class "Default")
      (node (ref "C12") (pin "1") (pinfunction "1_1") (pintype "passive"))
      (node (ref "IC11") (pin "1") (pinfunction "OUT_1") (pintype "output"))
      (node (ref "R52") (pin "2") (pinfunction "2_2") (pintype "passive"))
    )
    (net (code "95") (name "Net-(IC13-AVDD)") (class "Default")
      (node (ref "C42") (pin "2") (pinfunction "2_2") (pintype "passive"))
      (node (ref "C43") (pin "1") (pinfunction "1_1") (pintype "passive"))
      (node (ref "C44") (pin "1") (pinfunction "1_1") (pintype "passive"))
      (node (ref "C45") (pin "1") (pinfunction "1_1") (pintype "passive"))
      (node (ref "C46") (pin "1") (pinfunction "1_1") (pintype "passive"))
      (node (ref "C47") (pin "2") (pinfunction "2_2") (pintype "passive"))
      (node (ref "IC13") (pin "19") (pinfunction "AVDD_2_19") (pintype "power_in"))
      (node (ref "IC13") (pin "21") (pinfunction "AVDD_3_21") (pintype "power_in"))
      (node (ref "IC13") (pin "22") (pinfunction "AVDD_4_22") (pintype "power_in"))
      (node (ref "IC13") (pin "54") (pinfunction "AVDD1_54") (pintype "power_in"))
      (node (ref "IC13") (pin "56") (pinfunction "AVDD_5_56") (pintype "power_in"))
      (node (ref "IC13") (pin "59") (pinfunction "AVDD_59") (pintype "power_in"))
      (node (ref "R64") (pin "2") (pinfunction "2_2") (pintype "passive"))
    )
    (net (code "96") (name "Net-(IC13-CLK)") (class "Default")
      (node (ref "IC13") (pin "37") (pinfunction "CLK_37") (pintype "input"))
      (node (ref "JP7") (pin "2") (pinfunction "2_2") (pintype "passive"))
    )
    (net (code "97") (name "Net-(IC13-CLKSEL)") (class "Default")
      (node (ref "IC13") (pin "52") (pinfunction "CLKSEL_52") (pintype "input"))
      (node (ref "R63") (pin "1") (pinfunction "1_1") (pintype "passive"))
    )
    (net (code "98") (name "Net-(IC13-IN1N)") (class "Default")
      (node (ref "C19") (pin "2") (pinfunction "2_2") (pintype "passive"))
      (node (ref "C30") (pin "1") (pinfunction "1_1") (pintype "passive"))
      (node (ref "IC13") (pin "15") (pinfunction "IN1N_15") (pintype "input"))
      (node (ref "R55") (pin "2") (pinfunction "2_2") (pintype "passive"))
    )
    (net (code "99") (name "Net-(IC13-IN1P)") (class "Default")
      (node (ref "C20") (pin "2") (pinfunction "2_2") (pintype "passive"))
      (node (ref "C30") (pin "2") (pinfunction "2_2") (pintype "passive"))
      (node (ref "IC13") (pin "16") (pinfunction "IN1P_16") (pintype "input"))
      (node (ref "R54") (pin "2") (pinfunction "2_2") (pintype "passive"))
    )
    (net (code "100") (name "Net-(IC13-IN2N)") (class "Default")
      (node (ref "C17") (pin "2") (pinfunction "2_2") (pintype "passive"))
      (node (ref "C31") (pin "1") (pinfunction "1_1") (pintype "passive"))
      (node (ref "IC13") (pin "13") (pinfunction "IN2N_13") (pintype "input"))
      (node (ref "R57") (pin "2") (pinfunction "2_2") (pintype "passive"))
    )
    (net (code "101") (name "Net-(IC13-IN2P)") (class "Default")
      (node (ref "C18") (pin "2") (pinfunction "2_2") (pintype "passive"))
      (node (ref "C31") (pin "2") (pinfunction "2_2") (pintype "passive"))
      (node (ref "IC13") (pin "14") (pinfunction "IN2P_14") (pintype "input"))
      (node (ref "R56") (pin "2") (pinfunction "2_2") (pintype "passive"))
    )
    (net (code "102") (name "Net-(IC13-IN3N)") (class "Default")
      (node (ref "C32") (pin "1") (pinfunction "1_1") (pintype "passive"))
      (node (ref "C39") (pin "2") (pinfunction "2_2") (pintype "passive"))
      (node (ref "IC13") (pin "11") (pinfunction "IN3N_11") (pintype "input"))
      (node (ref "R59") (pin "2") (pinfunction "2_2") (pintype "passive"))
    )
    (net (code "103") (name "Net-(IC13-IN3P)") (class "Default")
      (node (ref "C32") (pin "2") (pinfunction "2_2") (pintype "passive"))
      (node (ref "C38") (pin "2") (pinfunction "2_2") (pintype "passive"))
      (node (ref "IC13") (pin "12") (pinfunction "IN3P_12") (pintype "input"))
      (node (ref "R58") (pin "2") (pinfunction "2_2") (pintype "passive"))
    )
    (net (code "104") (name "Net-(IC13-IN4N)") (class "Default")
      (node (ref "C33") (pin "1") (pinfunction "1_1") (pintype "passive"))
      (node (ref "C41") (pin "2") (pinfunction "2_2") (pintype "passive"))
      (node (ref "IC13") (pin "9") (pinfunction "IN4N_9") (pintype "input"))
      (node (ref "R61") (pin "2") (pinfunction "2_2") (pintype "passive"))
    )
    (net (code "105") (name "Net-(IC13-IN4P)") (class "Default")
      (node (ref "C33") (pin "2") (pinfunction "2_2") (pintype "passive"))
      (node (ref "C40") (pin "2") (pinfunction "2_2") (pintype "passive"))
      (node (ref "IC13") (pin "10") (pinfunction "IN4P_10") (pintype "input"))
      (node (ref "R60") (pin "2") (pinfunction "2_2") (pintype "passive"))
    )
    (net (code "106") (name "Net-(IC13-VCAP1)") (class "Default")
      (node (ref "C21") (pin "2") (pinfunction "2_2") (pintype "passive"))
      (node (ref "IC13") (pin "28") (pinfunction "VCAP1_28") (pintype "passive"))
    )
    (net (code "107") (name "Net-(IC13-VCAP2)") (class "Default")
      (node (ref "C15") (pin "2") (pinfunction "2_2") (pintype "passive"))
      (node (ref "IC13") (pin "30") (pinfunction "VCAP2_30") (pintype "passive"))
    )
    (net (code "108") (name "Net-(IC13-VCAP3)") (class "Default")
      (node (ref "C13") (pin "2") (pinfunction "2_2") (pintype "passive"))
      (node (ref "C14") (pin "1") (pinfunction "1_1") (pintype "passive"))
      (node (ref "IC13") (pin "55") (pinfunction "VCAP3_55") (pintype "passive"))
    )
    (net (code "109") (name "Net-(IC13-VCAP4)") (class "Default")
      (node (ref "C11") (pin "2") (pinfunction "2_2") (pintype "passive"))
      (node (ref "IC13") (pin "26") (pinfunction "VCAP4_26") (pintype "output"))
    )
    (net (code "110") (name "Net-(IC13-VREFP)") (class "Default")
      (node (ref "C16") (pin "1") (pinfunction "1_1") (pintype "passive"))
      (node (ref "C22") (pin "1") (pinfunction "1_1") (pintype "passive"))
      (node (ref "IC13") (pin "24") (pinfunction "VREFP_24") (pintype "bidirectional"))
      (node (ref "JP5") (pin "COM") (pinfunction "COM_COM") (pintype "passive"))
    )
    (net (code "111") (name "Net-(IC13-~{PWDN})") (class "Default")
      (node (ref "IC13") (pin "35") (pinfunction "~{PWDN}_35") (pintype "power_in"))
      (node (ref "R62") (pin "1") (pinfunction "1_1") (pintype "passive"))
    )
    (net (code "112") (name "Net-(IC14-EN)") (class "Default")
      (node (ref "C34") (pin "1") (pinfunction "1_1") (pintype "passive"))
      (node (ref "IC14") (pin "1") (pinfunction "IN_1") (pintype "input"))
      (node (ref "IC14") (pin "3") (pinfunction "EN_3") (pintype "input"))
      (node (ref "L3") (pin "P$1") (pinfunction "1_P$1") (pintype "passive"))
    )
    (net (code "113") (name "Net-(IC15-EN)") (class "Default")
      (node (ref "C35") (pin "1") (pinfunction "1_1") (pintype "passive"))
      (node (ref "IC15") (pin "2") (pinfunction "IN_2") (pintype "input"))
      (node (ref "IC15") (pin "3") (pinfunction "EN_3") (pintype "input"))
      (node (ref "L4") (pin "P$1") (pinfunction "1_P$1") (pintype "passive"))
    )
    (net (code "114") (name "Net-(ISEL1A_1B-COM)") (class "Default")
      (node (ref "F4") (pin "1") (pinfunction "1_1") (pintype "passive"))
      (node (ref "ISEL1A_1") (pin "4") (pinfunction "COM_4") (pintype "passive"))
      (node (ref "ISEL1A_1") (pin "9") (pinfunction "COM_9") (pintype "passive"))
    )
    (net (code "115") (name "Net-(ISEL1A_2B-COM)") (class "Default")
      (node (ref "F6") (pin "1") (pinfunction "1_1") (pintype "passive"))
      (node (ref "ISEL1A_2") (pin "4") (pinfunction "COM_4") (pintype "passive"))
      (node (ref "ISEL1A_2") (pin "9") (pinfunction "COM_9") (pintype "passive"))
    )
    (net (code "116") (name "Net-(ISEL10A_1B-COM)") (class "Default")
      (node (ref "F3") (pin "1") (pinfunction "1_1") (pintype "passive"))
      (node (ref "ISEL10A_1") (pin "11") (pinfunction "COM_11") (pintype "passive"))
      (node (ref "ISEL10A_1") (pin "21") (pinfunction "COM_21") (pintype "passive"))
    )
    (net (code "117") (name "Net-(ISEL10A_1B-NC)") (class "Default")
      (node (ref "ISEL10A_1") (pin "12") (pinfunction "NC_12") (pintype "passive"))
      (node (ref "ISEL10A_1") (pin "22") (pinfunction "NC_22") (pintype "passive"))
      (node (ref "R33") (pin "1") (pinfunction "1_1") (pintype "passive"))
      (node (ref "R36") (pin "2") (pinfunction "2_2") (pintype "passive"))
      (node (ref "R36") (pin "2S") (pinfunction "2S_2S") (pintype "passive"))
    )
    (net (code "118") (name "Net-(ISEL10A_1B-NO)") (class "Default")
      (node (ref "F4") (pin "2") (pinfunction "2_2") (pintype "passive"))
      (node (ref "ISEL10A_1") (pin "14") (pinfunction "NO_14") (pintype "passive"))
      (node (ref "ISEL10A_1") (pin "24") (pinfunction "NO_24") (pintype "passive"))
    )
    (net (code "119") (name "Net-(ISEL10A_2B-COM)") (class "Default")
      (node (ref "F5") (pin "2") (pinfunction "2_2") (pintype "passive"))
      (node (ref "ISEL10A_2") (pin "11") (pinfunction "COM_11") (pintype "passive"))
      (node (ref "ISEL10A_2") (pin "21") (pinfunction "COM_21") (pintype "passive"))
    )
    (net (code "120") (name "Net-(ISEL10A_2B-NC)") (class "Default")
      (node (ref "ISEL10A_2") (pin "12") (pinfunction "NC_12") (pintype "passive"))
      (node (ref "ISEL10A_2") (pin "22") (pinfunction "NC_22") (pintype "passive"))
      (node (ref "R43") (pin "1") (pinfunction "1_1") (pintype "passive"))
      (node (ref "R46") (pin "2") (pinfunction "2_2") (pintype "passive"))
      (node (ref "R46") (pin "2S") (pinfunction "2S_2S") (pintype "passive"))
    )
    (net (code "121") (name "Net-(ISEL10A_2B-NO)") (class "Default")
      (node (ref "F6") (pin "2") (pinfunction "2_2") (pintype "passive"))
      (node (ref "ISEL10A_2") (pin "14") (pinfunction "NO_14") (pintype "passive"))
      (node (ref "ISEL10A_2") (pin "24") (pinfunction "NO_24") (pintype "passive"))
    )
    (net (code "122") (name "Net-(JP5-PadNO)") (class "Default")
      (node (ref "JP5") (pin "NO") (pinfunction "NO_NO") (pintype "passive"))
      (node (ref "R51") (pin "1") (pinfunction "1_1") (pintype "passive"))
      (node (ref "R52") (pin "1") (pinfunction "1_1") (pintype "passive"))
    )
    (net (code "123") (name "Net-(JP6-PadCOM)") (class "Default")
      (node (ref "JP6") (pin "COM") (pinfunction "COM_COM") (pintype "passive"))
      (node (ref "R63") (pin "2") (pinfunction "2_2") (pintype "passive"))
    )
    (net (code "124") (name "Net-(L1-1)") (class "Default")
      (node (ref "L1") (pin "P$1") (pinfunction "1_P$1") (pintype "passive"))
      (node (ref "R12") (pin "2") (pinfunction "2_2") (pintype "passive"))
      (node (ref "R8") (pin "2") (pinfunction "2_2") (pintype "passive"))
    )
    (net (code "125") (name "Net-(L2-1)") (class "Default")
      (node (ref "L2") (pin "P$1") (pinfunction "1_P$1") (pintype "passive"))
      (node (ref "R22") (pin "2") (pinfunction "2_2") (pintype "passive"))
      (node (ref "R25") (pin "2") (pinfunction "2_2") (pintype "passive"))
    )
    (net (code "126") (name "Net-(OK1-A)") (class "Default")
      (node (ref "OK1") (pin "1") (pinfunction "A_1") (pintype "passive"))
      (node (ref "R3") (pin "1") (pinfunction "1_1") (pintype "passive"))
    )
    (net (code "127") (name "Net-(OK1-S2)") (class "Default")
      (node (ref "OK1") (pin "3") (pinfunction "S2_3") (pintype "passive"))
      (node (ref "Q1") (pin "2") (pinfunction "D_2") (pintype "passive"))
      (node (ref "Q1") (pin "4") (pinfunction "D_4") (pintype "passive"))
    )
    (net (code "128") (name "Net-(OK2-A)") (class "Default")
      (node (ref "OK2") (pin "1") (pinfunction "A_1") (pintype "passive"))
      (node (ref "R6") (pin "2") (pinfunction "2_2") (pintype "passive"))
    )
    (net (code "129") (name "Net-(OK2-S2)") (class "Default")
      (node (ref "OK2") (pin "3") (pinfunction "S2_3") (pintype "passive"))
      (node (ref "R9") (pin "1") (pinfunction "1_1") (pintype "passive"))
    )
    (net (code "130") (name "Net-(OK3-A)") (class "Default")
      (node (ref "OK3") (pin "1") (pinfunction "A_1") (pintype "passive"))
      (node (ref "R19") (pin "1") (pinfunction "1_1") (pintype "passive"))
    )
    (net (code "131") (name "Net-(OK3-S2)") (class "Default")
      (node (ref "OK3") (pin "3") (pinfunction "S2_3") (pintype "passive"))
      (node (ref "Q3") (pin "2") (pinfunction "D_2") (pintype "passive"))
      (node (ref "Q3") (pin "4") (pinfunction "D_4") (pintype "passive"))
    )
    (net (code "132") (name "Net-(OK4-A)") (class "Default")
      (node (ref "OK4") (pin "1") (pinfunction "A_1") (pintype "passive"))
      (node (ref "R21") (pin "2") (pinfunction "2_2") (pintype "passive"))
    )
    (net (code "133") (name "Net-(OK4-S2)") (class "Default")
      (node (ref "OK4") (pin "3") (pinfunction "S2_3") (pintype "passive"))
      (node (ref "R23") (pin "1") (pinfunction "1_1") (pintype "passive"))
    )
    (net (code "134") (name "Net-(Q1-S)") (class "Default")
      (node (ref "Q1") (pin "3") (pinfunction "S_3") (pintype "passive"))
      (node (ref "Q2") (pin "1") (pinfunction "G_1") (pintype "passive"))
      (node (ref "R1") (pin "2") (pinfunction "2_2") (pintype "passive"))
    )
    (net (code "135") (name "Net-(Q3-S)") (class "Default")
      (node (ref "Q3") (pin "3") (pinfunction "S_3") (pintype "passive"))
      (node (ref "Q4") (pin "1") (pinfunction "G_1") (pintype "passive"))
      (node (ref "R18") (pin "2") (pinfunction "2_2") (pintype "passive"))
    )
    (net (code "136") (name "Net-(Q5-D)") (class "Default")
      (node (ref "Q5") (pin "3") (pinfunction "D_3") (pintype "passive"))
      (node (ref "Q6") (pin "3") (pinfunction "D_3") (pintype "passive"))
    )
    (net (code "137") (name "Net-(Q7-D)") (class "Default")
      (node (ref "Q7") (pin "3") (pinfunction "D_3") (pintype "passive"))
      (node (ref "Q8") (pin "3") (pinfunction "D_3") (pintype "passive"))
    )
    (net (code "138") (name "Net-(R8-Pad1)") (class "Default")
      (node (ref "R8") (pin "1") (pinfunction "1_1") (pintype "passive"))
      (node (ref "R9") (pin "2") (pinfunction "2_2") (pintype "passive"))
    )
    (net (code "139") (name "Net-(R12-Pad1)") (class "Default")
      (node (ref "R12") (pin "1") (pinfunction "1_1") (pintype "passive"))
      (node (ref "R13") (pin "2") (pinfunction "2_2") (pintype "passive"))
    )
    (net (code "140") (name "Net-(R13-Pad1)") (class "Default")
      (node (ref "R13") (pin "1") (pinfunction "1_1") (pintype "passive"))
      (node (ref "R14") (pin "2") (pinfunction "2_2") (pintype "passive"))
    )
    (net (code "141") (name "Net-(R15-Pad1)") (class "Default")
      (node (ref "R15") (pin "1") (pinfunction "1_1") (pintype "passive"))
      (node (ref "R16") (pin "2") (pinfunction "2_2") (pintype "passive"))
    )
    (net (code "142") (name "Net-(R22-Pad1)") (class "Default")
      (node (ref "R22") (pin "1") (pinfunction "1_1") (pintype "passive"))
      (node (ref "R23") (pin "2") (pinfunction "2_2") (pintype "passive"))
    )
    (net (code "143") (name "Net-(R25-Pad1)") (class "Default")
      (node (ref "R25") (pin "1") (pinfunction "1_1") (pintype "passive"))
      (node (ref "R26") (pin "2") (pinfunction "2_2") (pintype "passive"))
    )
    (net (code "144") (name "Net-(R26-Pad1)") (class "Default")
      (node (ref "R26") (pin "1") (pinfunction "1_1") (pintype "passive"))
      (node (ref "R27") (pin "2") (pinfunction "2_2") (pintype "passive"))
    )
    (net (code "145") (name "Net-(R28-Pad1)") (class "Default")
      (node (ref "R28") (pin "1") (pinfunction "1_1") (pintype "passive"))
      (node (ref "R29") (pin "2") (pinfunction "2_2") (pintype "passive"))
    )
    (net (code "146") (name "Net-(R38-Pad1)") (class "Default")
      (node (ref "R38") (pin "1") (pinfunction "1_1") (pintype "passive"))
      (node (ref "R39") (pin "2") (pinfunction "2_2") (pintype "passive"))
    )
    (net (code "147") (name "Net-(R48-Pad1)") (class "Default")
      (node (ref "R48") (pin "1") (pinfunction "1_1") (pintype "passive"))
      (node (ref "R49") (pin "2") (pinfunction "2_2") (pintype "passive"))
    )
    (net (code "148") (name "USEL1#1") (class "Default")
      (node (ref "IC2") (pin "8") (pinfunction "IN_8") (pintype "input"))
      (node (ref "R6") (pin "1") (pinfunction "1_1") (pintype "passive"))
      (node (ref "X3") (pin "5") (pinfunction "1_5") (pintype "passive"))
    )
    (net (code "149") (name "USEL1#2") (class "Default")
      (node (ref "IC5") (pin "8") (pinfunction "IN_8") (pintype "input"))
      (node (ref "R21") (pin "1") (pinfunction "1_1") (pintype "passive"))
      (node (ref "X3") (pin "6") (pinfunction "1_6") (pintype "passive"))
    )
    (net (code "150") (name "USEL1#3") (class "Default")
      (node (ref "IC7") (pin "8") (pinfunction "IN_8") (pintype "input"))
      (node (ref "X3") (pin "11") (pinfunction "1_11") (pintype "passive"))
    )
    (net (code "151") (name "USEL1#4") (class "Default")
      (node (ref "IC9") (pin "8") (pinfunction "IN_8") (pintype "input"))
      (node (ref "X3") (pin "12") (pinfunction "1_12") (pintype "passive"))
    )
    (net (code "152") (name "USEL10#1") (class "Default")
      (node (ref "IC2") (pin "1") (pinfunction "IN_1") (pintype "input"))
      (node (ref "X3") (pin "7") (pinfunction "1_7") (pintype "passive"))
    )
    (net (code "153") (name "USEL10#2") (class "Default")
      (node (ref "IC5") (pin "1") (pinfunction "IN_1") (pintype "input"))
      (node (ref "X3") (pin "8") (pinfunction "1_8") (pintype "passive"))
    )
    (net (code "154") (name "USEL10#3") (class "Default")
      (node (ref "IC7") (pin "1") (pinfunction "IN_1") (pintype "input"))
      (node (ref "X3") (pin "13") (pinfunction "1_13") (pintype "passive"))
    )
    (net (code "155") (name "USEL10#4") (class "Default")
      (node (ref "IC9") (pin "1") (pinfunction "IN_1") (pintype "input"))
      (node (ref "X3") (pin "14") (pinfunction "1_14") (pintype "passive"))
    )
    (net (code "156") (name "USEL100#1") (class "Default")
      (node (ref "IC2") (pin "16") (pinfunction "IN_16") (pintype "input"))
      (node (ref "X3") (pin "9") (pinfunction "1_9") (pintype "passive"))
    )
    (net (code "157") (name "USEL100#2") (class "Default")
      (node (ref "IC5") (pin "16") (pinfunction "IN_16") (pintype "input"))
      (node (ref "X3") (pin "10") (pinfunction "1_10") (pintype "passive"))
    )
    (net (code "158") (name "unconnected-(IC12-TEMP-Pad3)") (class "Default")
      (node (ref "IC12") (pin "3") (pinfunction "TEMP_3") (pintype "input"))
    )
    (net (code "159") (name "unconnected-(IC12-TRIM{slash}NR-Pad5)") (class "Default")
      (node (ref "IC12") (pin "5") (pinfunction "TRIM/NR_5") (pintype "input"))
    )
    (net (code "160") (name "unconnected-(IC13-GPIO1-Pad42)") (class "Default")
      (node (ref "IC13") (pin "42") (pinfunction "GPIO1_42") (pintype "bidirectional"))
    )
    (net (code "161") (name "unconnected-(IC13-GPIO2-Pad44)") (class "Default")
      (node (ref "IC13") (pin "44") (pinfunction "GPIO2_44") (pintype "bidirectional"))
    )
    (net (code "162") (name "unconnected-(IC13-GPIO3-Pad45)") (class "Default")
      (node (ref "IC13") (pin "45") (pinfunction "GPIO3_45") (pintype "bidirectional"))
    )
    (net (code "163") (name "unconnected-(IC13-GPIO4-Pad46)") (class "Default")
      (node (ref "IC13") (pin "46") (pinfunction "GPIO4_46") (pintype "bidirectional"))
    )
    (net (code "164") (name "unconnected-(IC13-IN5N(NC)-Pad7)") (class "Default")
      (node (ref "IC13") (pin "7") (pinfunction "IN5N(NC)_7") (pintype "input"))
    )
    (net (code "165") (name "unconnected-(IC13-IN5P(NC)-Pad8)") (class "Default")
      (node (ref "IC13") (pin "8") (pinfunction "IN5P(NC)_8") (pintype "input"))
    )
    (net (code "166") (name "unconnected-(IC13-IN6N(NC)-Pad5)") (class "Default")
      (node (ref "IC13") (pin "5") (pinfunction "IN6N(NC)_5") (pintype "input"))
    )
    (net (code "167") (name "unconnected-(IC13-IN6P(NC)-Pad6)") (class "Default")
      (node (ref "IC13") (pin "6") (pinfunction "IN6P(NC)_6") (pintype "input"))
    )
    (net (code "168") (name "unconnected-(IC13-IN7N(NC)-Pad3)") (class "Default")
      (node (ref "IC13") (pin "3") (pinfunction "IN7N(NC)_3") (pintype "input"))
    )
    (net (code "169") (name "unconnected-(IC13-IN7P(NC)-Pad4)") (class "Default")
      (node (ref "IC13") (pin "4") (pinfunction "IN7P(NC)_4") (pintype "input"))
    )
    (net (code "170") (name "unconnected-(IC13-IN8N(NC)-Pad1)") (class "Default")
      (node (ref "IC13") (pin "1") (pinfunction "IN8N(NC)_1") (pintype "input"))
    )
    (net (code "171") (name "unconnected-(IC13-IN8P(NC)-Pad2)") (class "Default")
      (node (ref "IC13") (pin "2") (pinfunction "IN8P(NC)_2") (pintype "input"))
    )
    (net (code "172") (name "unconnected-(IC13-OPAMPN-Pad61)") (class "Default")
      (node (ref "IC13") (pin "61") (pinfunction "OPAMPN_61") (pintype "input"))
    )
    (net (code "173") (name "unconnected-(IC13-OPAMPOUT-Pad63)") (class "Default")
      (node (ref "IC13") (pin "63") (pinfunction "OPAMPOUT_63") (pintype "output"))
    )
    (net (code "174") (name "unconnected-(IC13-OPAMPP-Pad60)") (class "Default")
      (node (ref "IC13") (pin "60") (pinfunction "OPAMPP_60") (pintype "input"))
    )
    (net (code "175") (name "unconnected-(IC13-TESTN-Pad18)") (class "Default")
      (node (ref "IC13") (pin "18") (pinfunction "TESTN_18") (pintype "bidirectional"))
    )
    (net (code "176") (name "unconnected-(IC13-TESTP-Pad17)") (class "Default")
      (node (ref "IC13") (pin "17") (pinfunction "TESTP_17") (pintype "bidirectional"))
    )
    (net (code "177") (name "unconnected-(IC14-NR-Pad4)") (class "Default")
      (node (ref "IC14") (pin "4") (pinfunction "NR_4") (pintype "passive"))
    )
    (net (code "178") (name "unconnected-(IC15-NR-Pad4)") (class "Default")
      (node (ref "IC15") (pin "4") (pinfunction "NR_4") (pintype "passive"))
    )
    (net (code "179") (name "unconnected-(X2I-1-Pad17)") (class "Default")
      (node (ref "X2") (pin "17") (pinfunction "1_17") (pintype "passive"))
    )
    (net (code "180") (name "unconnected-(X2J-1-Pad18)") (class "Default")
      (node (ref "X2") (pin "18") (pinfunction "1_18") (pintype "passive"))
    )
    (net (code "181") (name "~{ADC_CS}") (class "Default")
      (node (ref "IC13") (pin "39") (pinfunction "~{CS}_39") (pintype "input"))
      (node (ref "X2") (pin "5") (pinfunction "1_5") (pintype "passive"))
    )
    (net (code "182") (name "~{ADC_DRDY}") (class "Default")
      (node (ref "IC13") (pin "47") (pinfunction "~{DRDY}_47") (pintype "output"))
      (node (ref "X2") (pin "7") (pinfunction "1_7") (pintype "passive"))
    )
    (net (code "183") (name "~{RESET}") (class "Default")
      (node (ref "IC13") (pin "36") (pinfunction "~{RESET}_36") (pintype "input"))
      (node (ref "X2") (pin "9") (pinfunction "1_9") (pintype "passive"))
    )
  )
)
